# STM32F407ZGT6_1_2.net
KiCad netlist of a schematic drawn in EasyEDA Pro
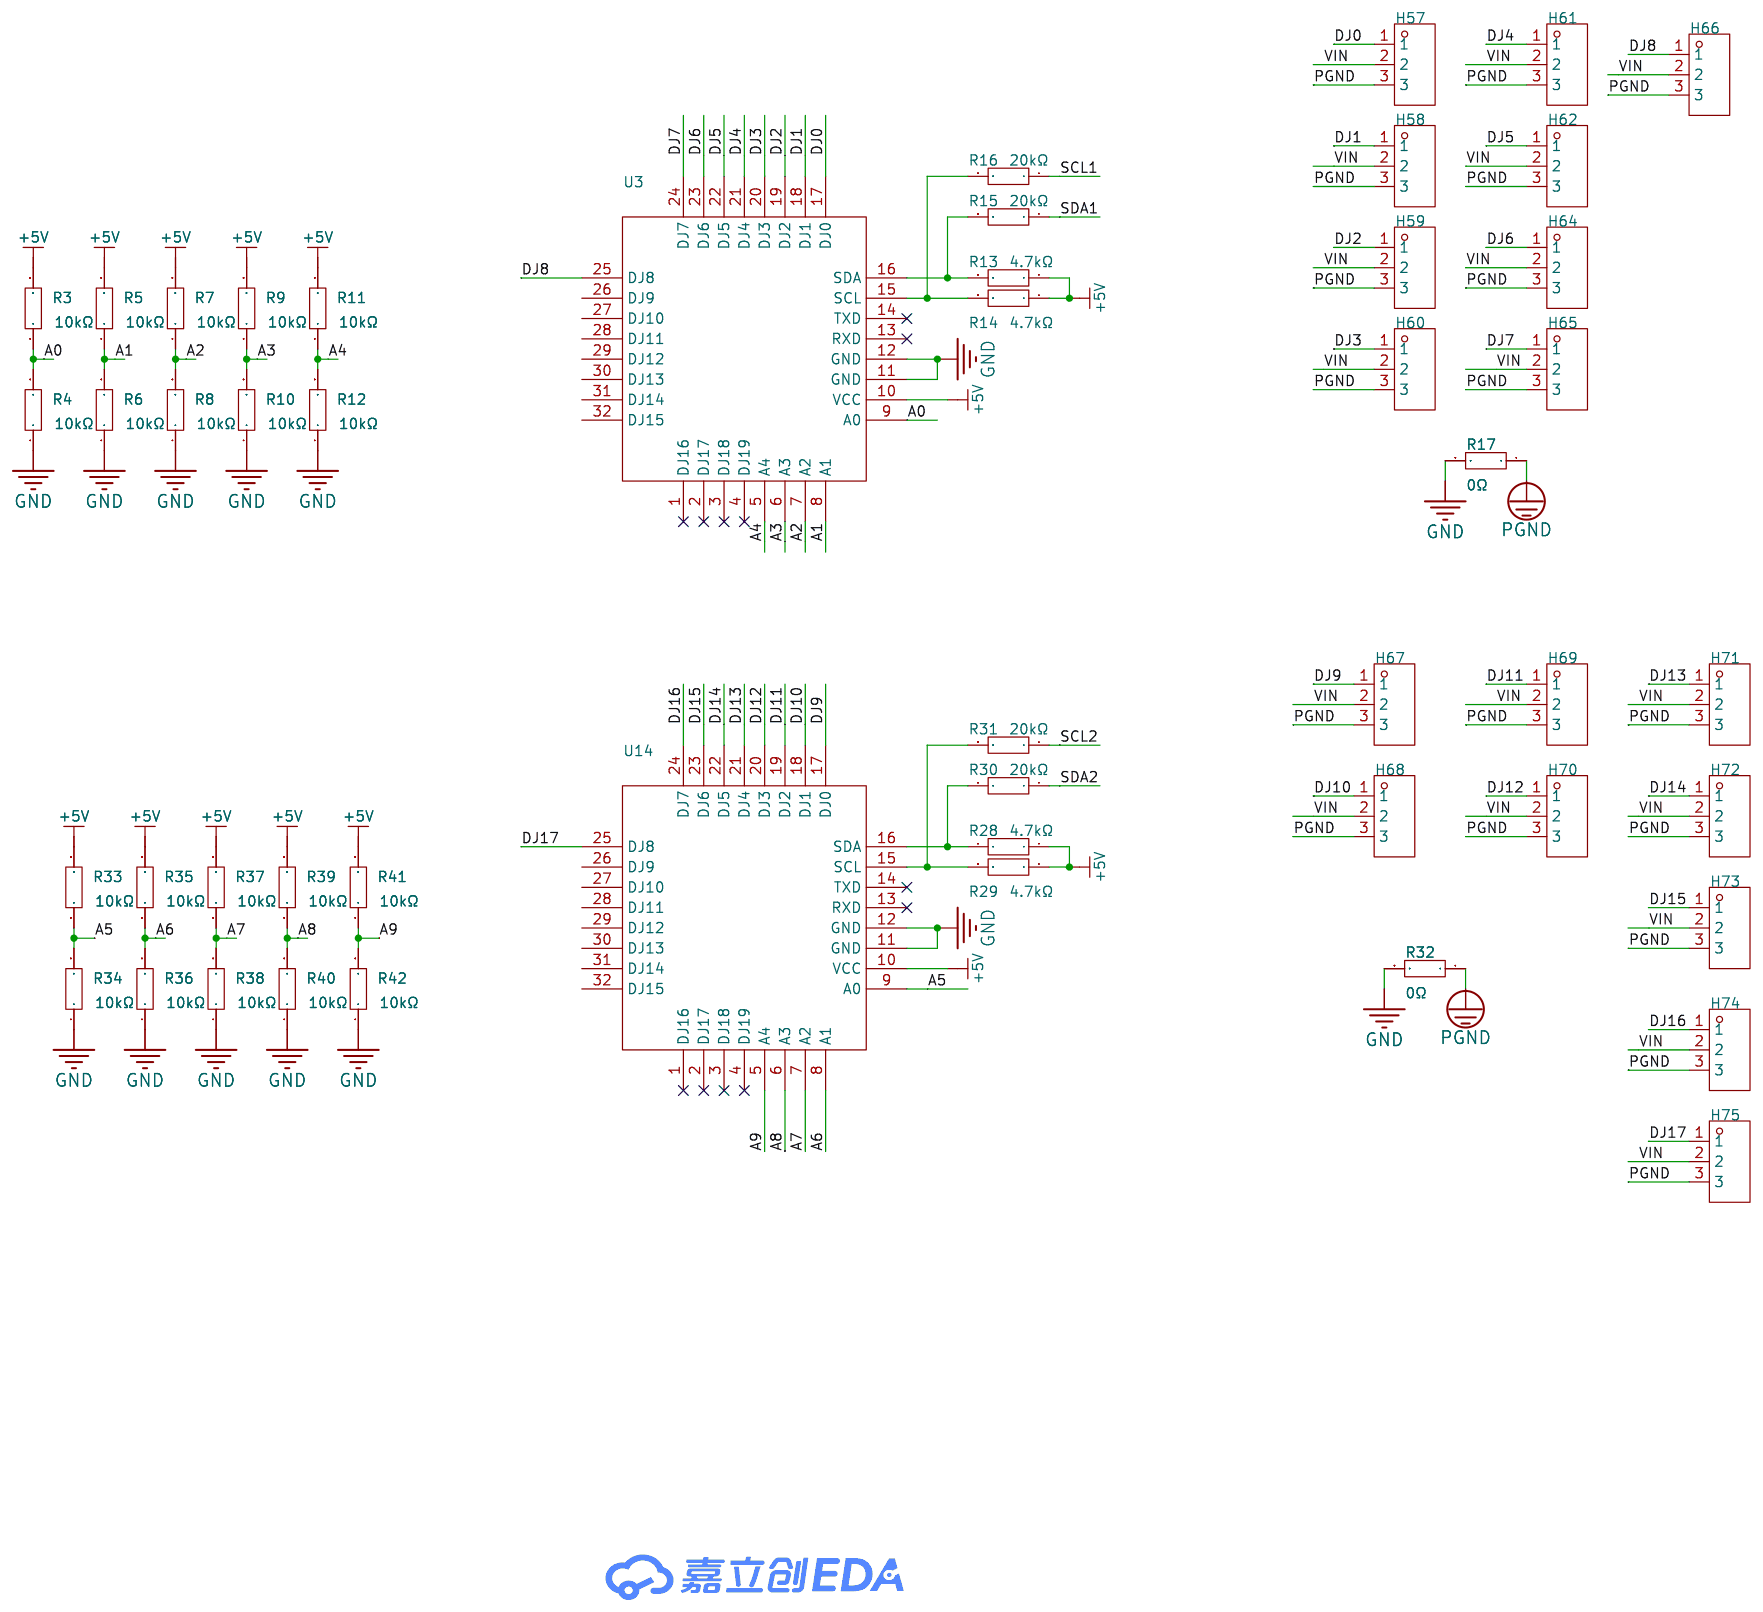
[diagram p0: PWM模块]
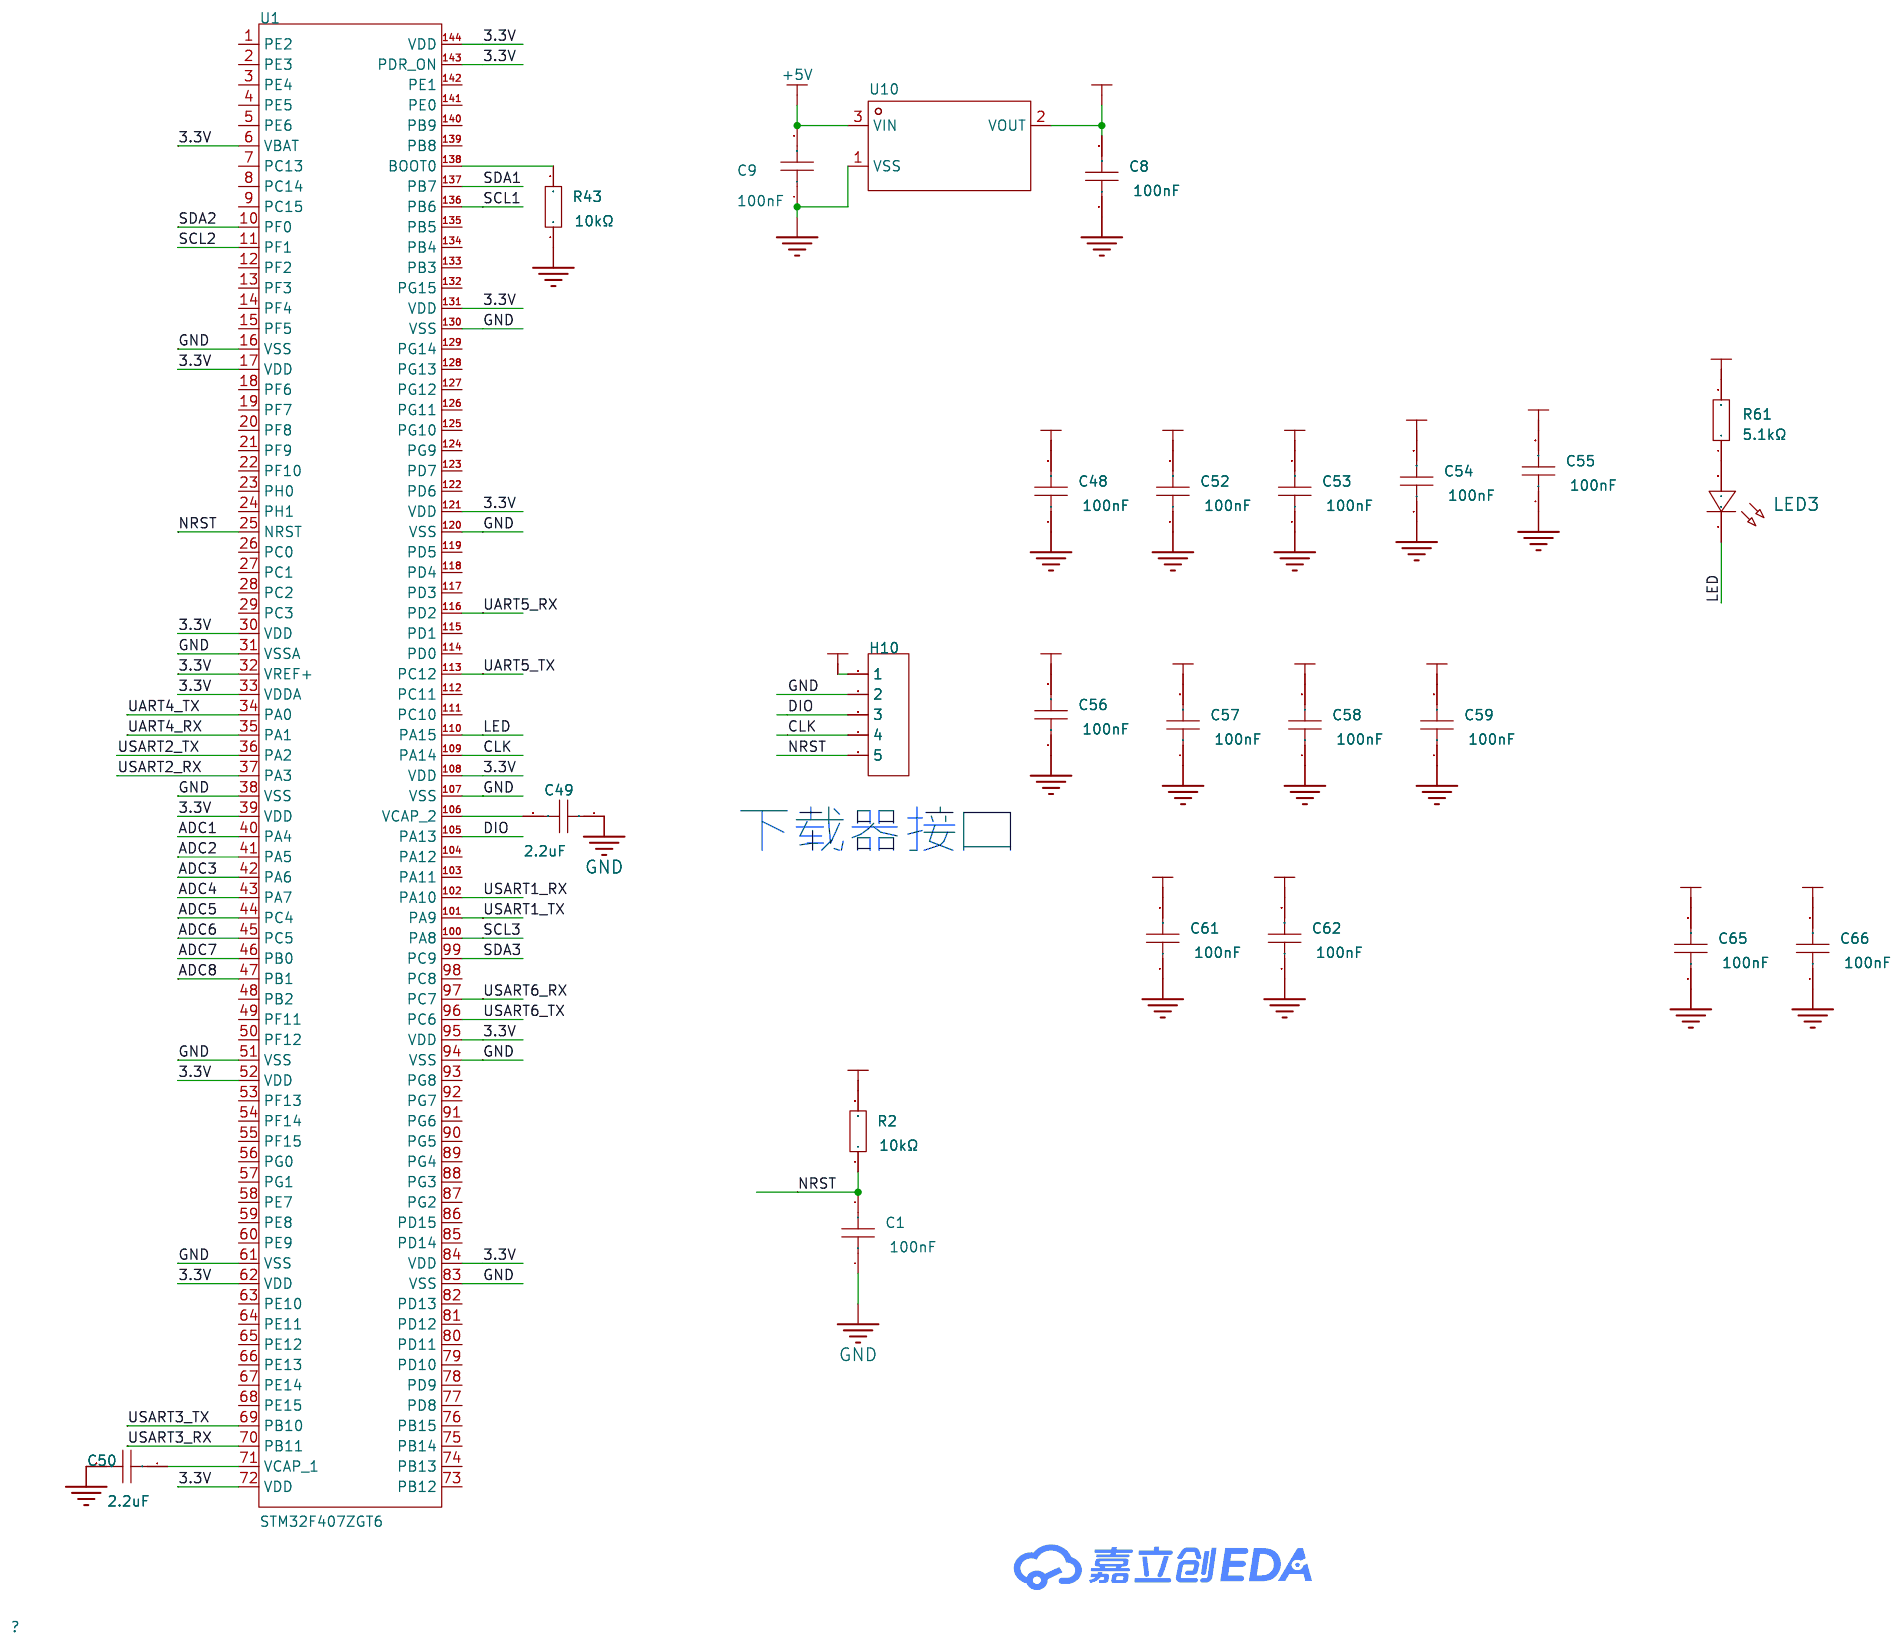
[diagram p1: 单片机模块]
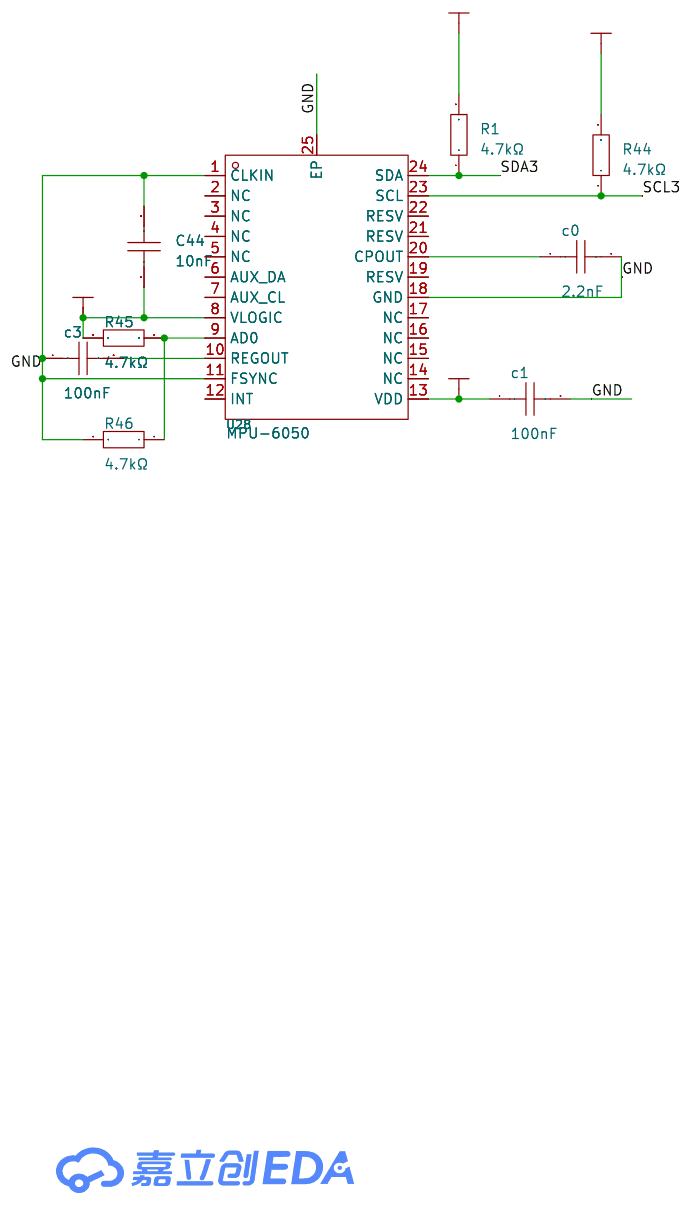
[diagram p2: IMU]
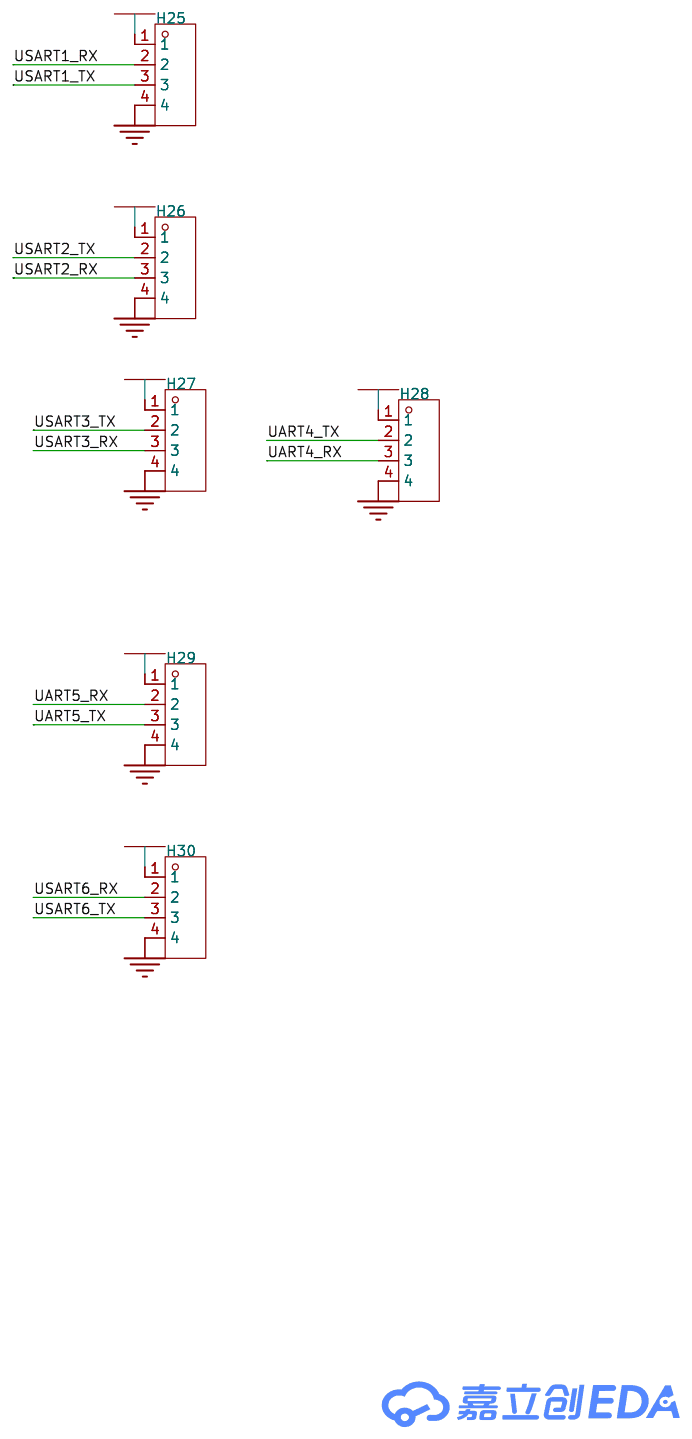
[diagram p3: 串口]
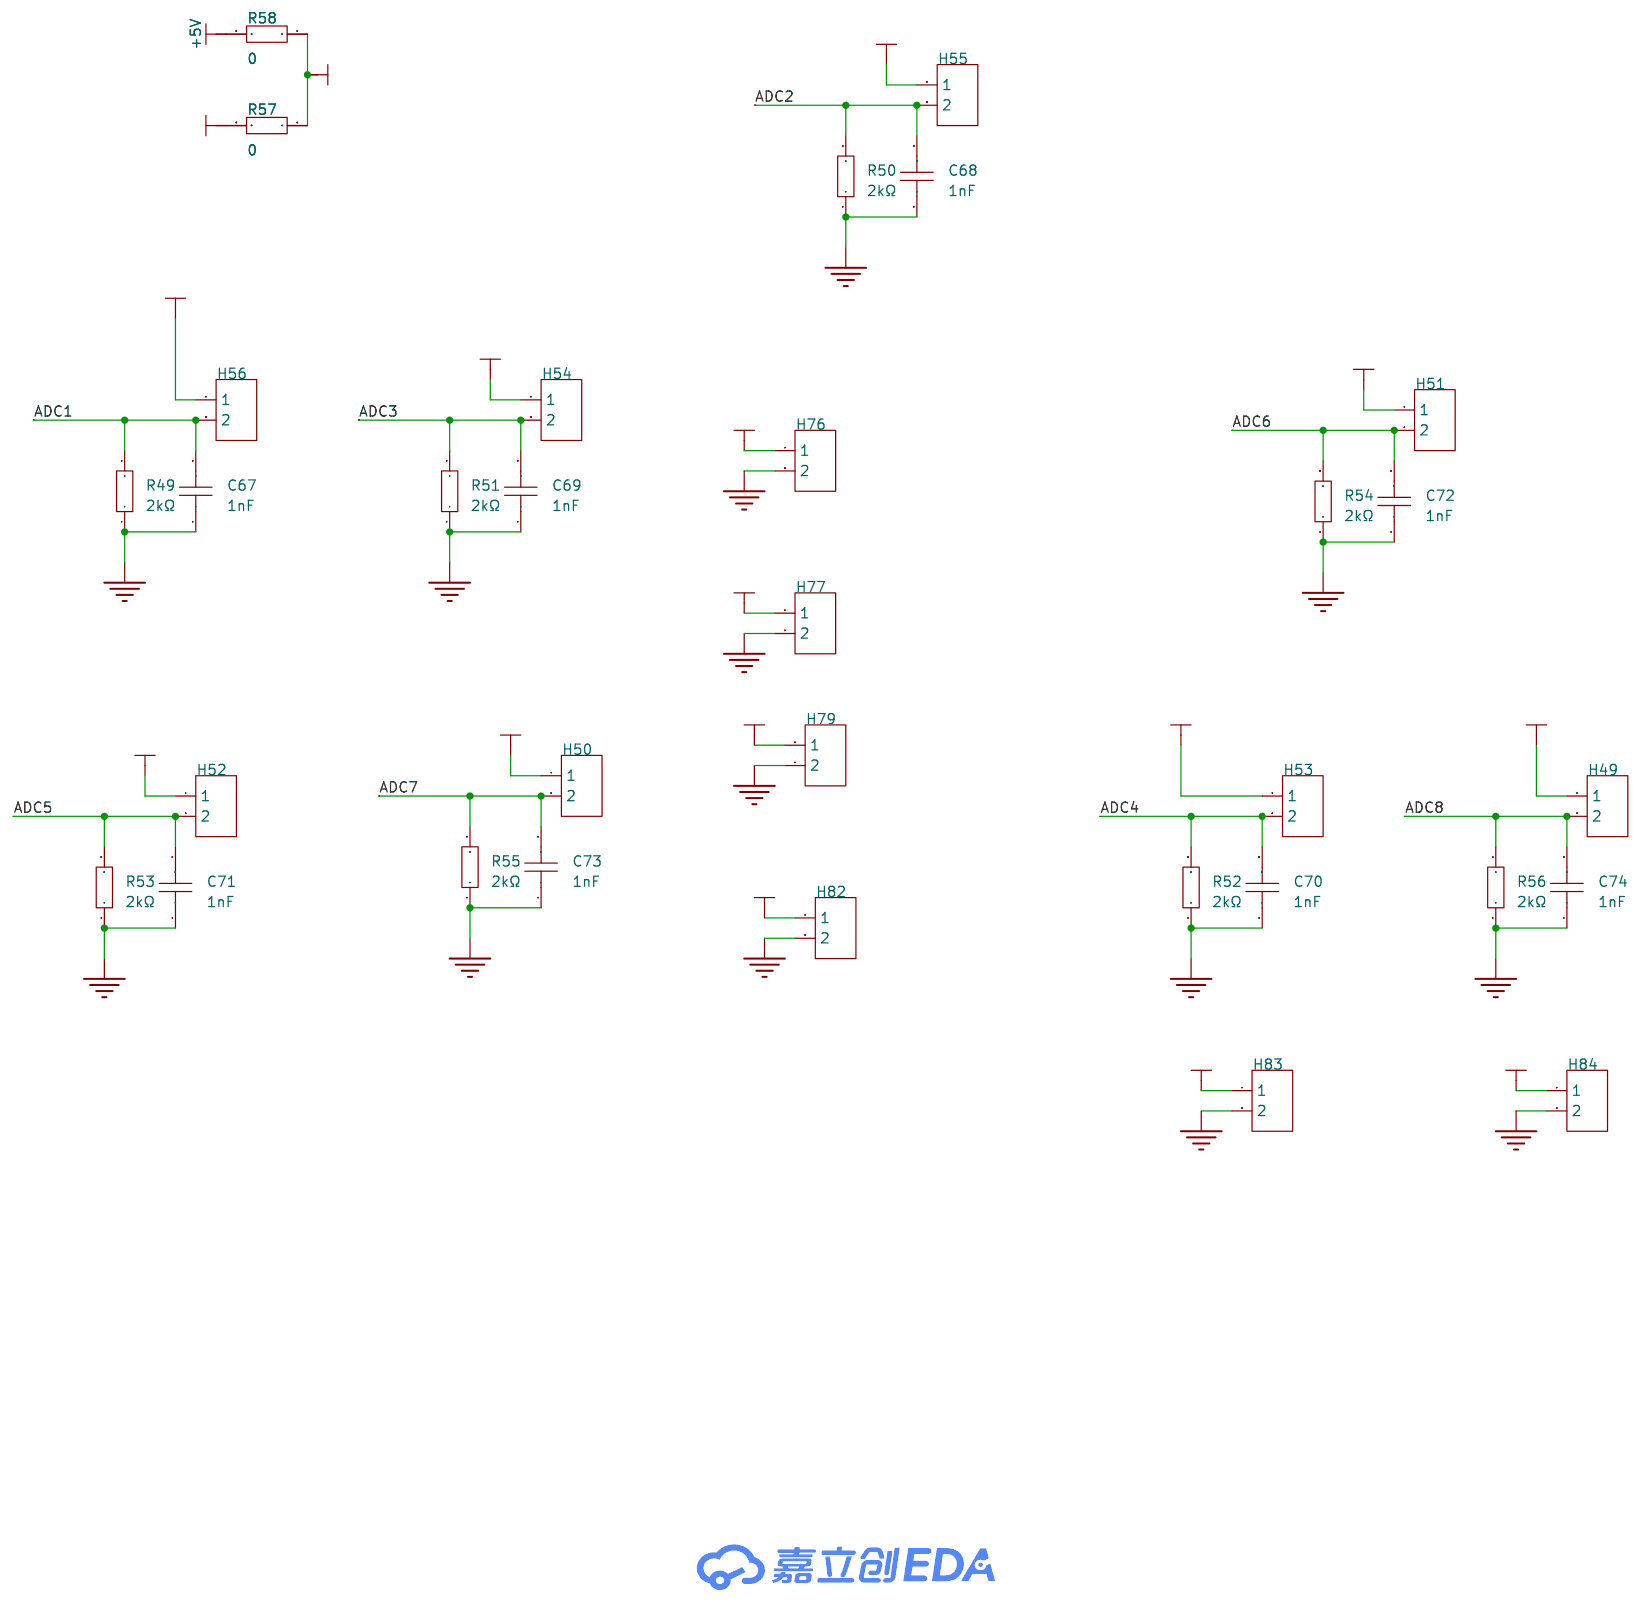
[diagram p4: ADC]
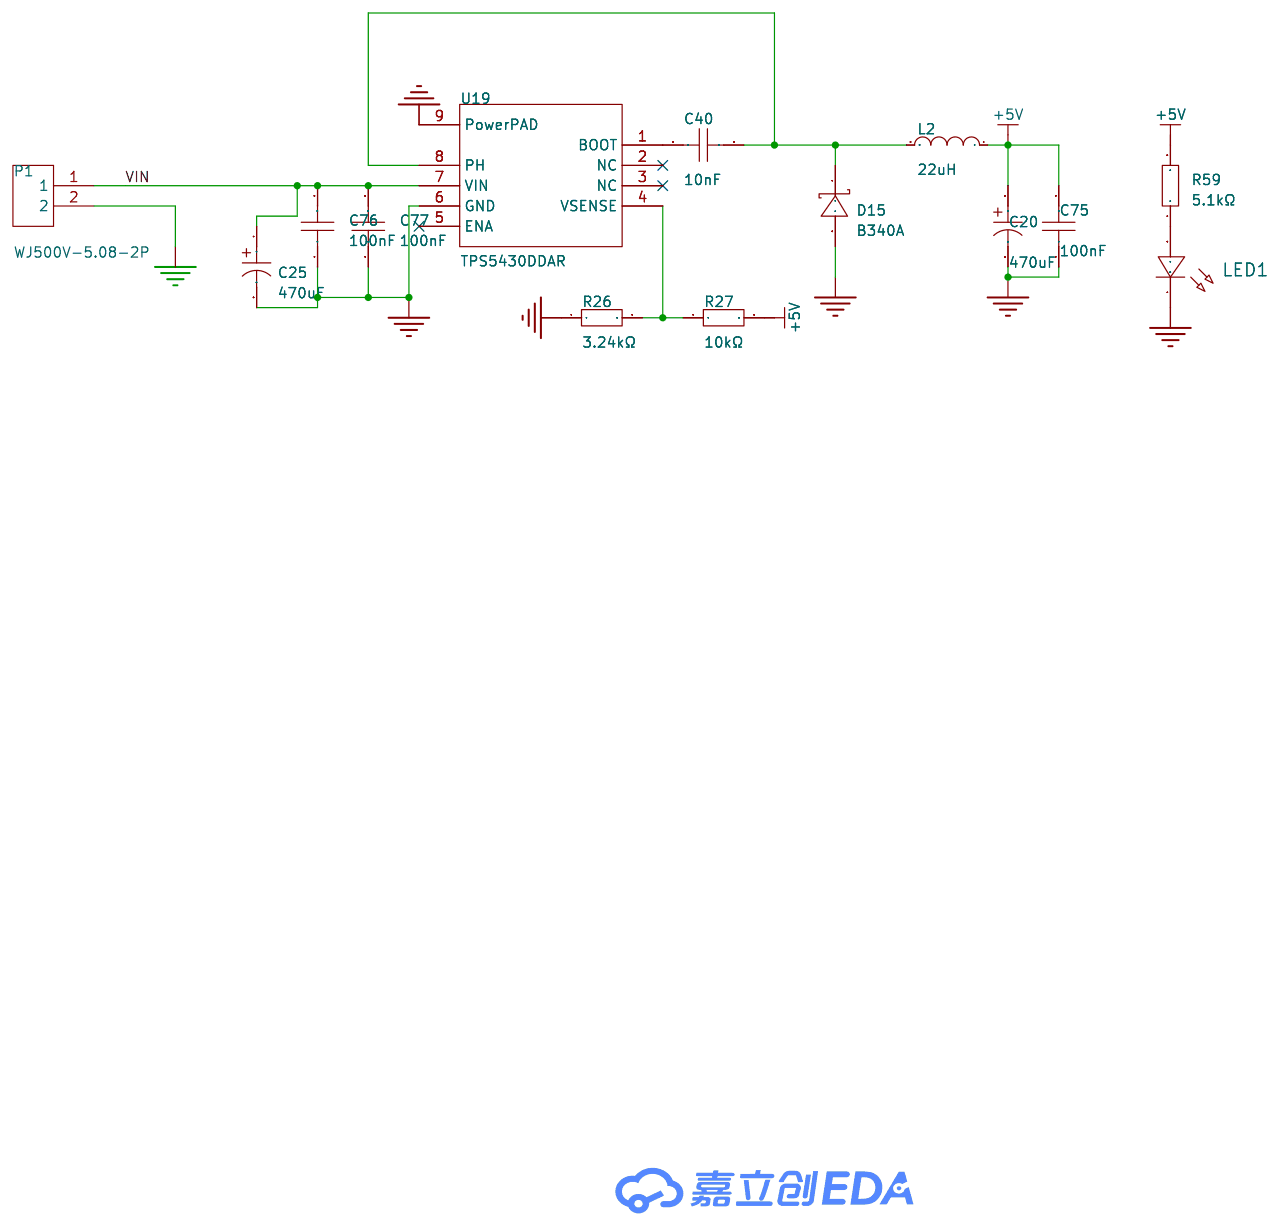
[diagram p5: 电源]

(export (version "E")
  (design (tool "Eeschema 10.0.6"))
  (components
    (comp (ref "H57")
      (value "~")
      (footprint "easyedapro:HDR-TH_3P-P2.54-V-F")
      (libsource (lib "easyedapro") (part "PM254V-11-03-H85"))
    )
    (comp (ref "H58")
      (value "~")
      (footprint "easyedapro:HDR-TH_3P-P2.54-V-F")
      (libsource (lib "easyedapro") (part "PM254V-11-03-H85"))
    )
    (comp (ref "H59")
      (value "~")
      (footprint "easyedapro:HDR-TH_3P-P2.54-V-F")
      (libsource (lib "easyedapro") (part "PM254V-11-03-H85"))
    )
    (comp (ref "H60")
      (value "~")
      (footprint "easyedapro:HDR-TH_3P-P2.54-V-F")
      (libsource (lib "easyedapro") (part "PM254V-11-03-H85"))
    )
    (comp (ref "H61")
      (value "~")
      (footprint "easyedapro:HDR-TH_3P-P2.54-V-F")
      (libsource (lib "easyedapro") (part "PM254V-11-03-H85"))
    )
    (comp (ref "H62")
      (value "~")
      (footprint "easyedapro:HDR-TH_3P-P2.54-V-F")
      (libsource (lib "easyedapro") (part "PM254V-11-03-H85"))
    )
    (comp (ref "H64")
      (value "~")
      (footprint "easyedapro:HDR-TH_3P-P2.54-V-F")
      (libsource (lib "easyedapro") (part "PM254V-11-03-H85"))
    )
    (comp (ref "H65")
      (value "~")
      (footprint "easyedapro:HDR-TH_3P-P2.54-V-F")
      (libsource (lib "easyedapro") (part "PM254V-11-03-H85"))
    )
    (comp (ref "H66")
      (value "~")
      (footprint "easyedapro:HDR-TH_3P-P2.54-V-F")
      (libsource (lib "easyedapro") (part "PM254V-11-03-H85"))
    )
    (comp (ref "H67")
      (value "~")
      (footprint "easyedapro:HDR-TH_3P-P2.54-V-F")
      (libsource (lib "easyedapro") (part "PM254V-11-03-H85"))
    )
    (comp (ref "H68")
      (value "~")
      (footprint "easyedapro:HDR-TH_3P-P2.54-V-F")
      (libsource (lib "easyedapro") (part "PM254V-11-03-H85"))
    )
    (comp (ref "H69")
      (value "~")
      (footprint "easyedapro:HDR-TH_3P-P2.54-V-F")
      (libsource (lib "easyedapro") (part "PM254V-11-03-H85"))
    )
    (comp (ref "H70")
      (value "~")
      (footprint "easyedapro:HDR-TH_3P-P2.54-V-F")
      (libsource (lib "easyedapro") (part "PM254V-11-03-H85"))
    )
    (comp (ref "H71")
      (value "~")
      (footprint "easyedapro:HDR-TH_3P-P2.54-V-F")
      (libsource (lib "easyedapro") (part "PM254V-11-03-H85"))
    )
    (comp (ref "H72")
      (value "~")
      (footprint "easyedapro:HDR-TH_3P-P2.54-V-F")
      (libsource (lib "easyedapro") (part "PM254V-11-03-H85"))
    )
    (comp (ref "H73")
      (value "~")
      (footprint "easyedapro:HDR-TH_3P-P2.54-V-F")
      (libsource (lib "easyedapro") (part "PM254V-11-03-H85"))
    )
    (comp (ref "H74")
      (value "~")
      (footprint "easyedapro:HDR-TH_3P-P2.54-V-F")
      (libsource (lib "easyedapro") (part "PM254V-11-03-H85"))
    )
    (comp (ref "H75")
      (value "~")
      (footprint "easyedapro:HDR-TH_3P-P2.54-V-F")
      (libsource (lib "easyedapro") (part "PM254V-11-03-H85"))
    )
    (comp (ref "R3")
      (value "10kΩ")
      (footprint "easyedapro:R0805")
      (fields
        (field (name "Manufacturer Part") "0402WGF1002TCE")
        (field (name "Manufacturer") "UNI-ROYAL(厚声)")
      )
      (libsource (lib "easyedapro") (part "电阻"))
    )
    (comp (ref "R4")
      (value "10kΩ")
      (footprint "easyedapro:R0805")
      (fields
        (field (name "Manufacturer Part") "0402WGF1002TCE")
        (field (name "Manufacturer") "UNI-ROYAL(厚声)")
      )
      (libsource (lib "easyedapro") (part "电阻"))
    )
    (comp (ref "R5")
      (value "10kΩ")
      (footprint "easyedapro:R0805")
      (fields
        (field (name "Manufacturer Part") "0402WGF1002TCE")
        (field (name "Manufacturer") "UNI-ROYAL(厚声)")
      )
      (libsource (lib "easyedapro") (part "电阻"))
    )
    (comp (ref "R6")
      (value "10kΩ")
      (footprint "easyedapro:R0805")
      (fields
        (field (name "Manufacturer Part") "0402WGF1002TCE")
        (field (name "Manufacturer") "UNI-ROYAL(厚声)")
      )
      (libsource (lib "easyedapro") (part "电阻"))
    )
    (comp (ref "R7")
      (value "10kΩ")
      (footprint "easyedapro:R0805")
      (fields
        (field (name "Manufacturer Part") "0402WGF1002TCE")
        (field (name "Manufacturer") "UNI-ROYAL(厚声)")
      )
      (libsource (lib "easyedapro") (part "电阻"))
    )
    (comp (ref "R8")
      (value "10kΩ")
      (footprint "easyedapro:R0805")
      (fields
        (field (name "Manufacturer Part") "0402WGF1002TCE")
        (field (name "Manufacturer") "UNI-ROYAL(厚声)")
      )
      (libsource (lib "easyedapro") (part "电阻"))
    )
    (comp (ref "R9")
      (value "10kΩ")
      (footprint "easyedapro:R0805")
      (fields
        (field (name "Manufacturer Part") "0402WGF1002TCE")
        (field (name "Manufacturer") "UNI-ROYAL(厚声)")
      )
      (libsource (lib "easyedapro") (part "电阻"))
    )
    (comp (ref "R10")
      (value "10kΩ")
      (footprint "easyedapro:R0805")
      (fields
        (field (name "Manufacturer Part") "0402WGF1002TCE")
        (field (name "Manufacturer") "UNI-ROYAL(厚声)")
      )
      (libsource (lib "easyedapro") (part "电阻"))
    )
    (comp (ref "R11")
      (value "10kΩ")
      (footprint "easyedapro:R0805")
      (fields
        (field (name "Manufacturer Part") "0402WGF1002TCE")
        (field (name "Manufacturer") "UNI-ROYAL(厚声)")
      )
      (libsource (lib "easyedapro") (part "电阻"))
    )
    (comp (ref "R12")
      (value "10kΩ")
      (footprint "easyedapro:R0805")
      (fields
        (field (name "Manufacturer Part") "0402WGF1002TCE")
        (field (name "Manufacturer") "UNI-ROYAL(厚声)")
      )
      (libsource (lib "easyedapro") (part "电阻"))
    )
    (comp (ref "R13")
      (value "4.7kΩ")
      (footprint "easyedapro:R0805")
      (fields
        (field (name "Manufacturer Part") "0402WGF4701TCE")
        (field (name "Manufacturer") "UNI-ROYAL(厚声)")
      )
      (libsource (lib "easyedapro") (part "电阻"))
    )
    (comp (ref "R14")
      (value "4.7kΩ")
      (footprint "easyedapro:R0805")
      (fields
        (field (name "Manufacturer Part") "0402WGF4701TCE")
        (field (name "Manufacturer") "UNI-ROYAL(厚声)")
      )
      (libsource (lib "easyedapro") (part "电阻"))
    )
    (comp (ref "R15")
      (value "20kΩ")
      (footprint "easyedapro:R0805")
      (fields (field (name "Manufacturer Part") "FRC0402F2002TS") (field (name "Manufacturer") "FOJAN(富捷)"))
      (libsource (lib "easyedapro") (part "电阻"))
    )
    (comp (ref "R16")
      (value "20kΩ")
      (footprint "easyedapro:R0805")
      (fields (field (name "Manufacturer Part") "FRC0402F2002TS") (field (name "Manufacturer") "FOJAN(富捷)"))
      (libsource (lib "easyedapro") (part "电阻"))
    )
    (comp (ref "R17")
      (value "0Ω")
      (footprint "easyedapro:R0805")
      (fields
        (field (name "Manufacturer Part") "0402WGF0000TCE")
        (field (name "Manufacturer") "UNI-ROYAL(厚声)")
      )
      (libsource (lib "easyedapro") (part "电阻"))
    )
    (comp (ref "R28")
      (value "4.7kΩ")
      (footprint "easyedapro:R0805")
      (fields
        (field (name "Manufacturer Part") "0402WGF4701TCE")
        (field (name "Manufacturer") "UNI-ROYAL(厚声)")
      )
      (libsource (lib "easyedapro") (part "电阻"))
    )
    (comp (ref "R29")
      (value "4.7kΩ")
      (footprint "easyedapro:R0805")
      (fields
        (field (name "Manufacturer Part") "0402WGF4701TCE")
        (field (name "Manufacturer") "UNI-ROYAL(厚声)")
      )
      (libsource (lib "easyedapro") (part "电阻"))
    )
    (comp (ref "R30")
      (value "20kΩ")
      (footprint "easyedapro:R0805")
      (fields (field (name "Manufacturer Part") "FRC0402F2002TS") (field (name "Manufacturer") "FOJAN(富捷)"))
      (libsource (lib "easyedapro") (part "电阻"))
    )
    (comp (ref "R31")
      (value "20kΩ")
      (footprint "easyedapro:R0805")
      (fields (field (name "Manufacturer Part") "FRC0402F2002TS") (field (name "Manufacturer") "FOJAN(富捷)"))
      (libsource (lib "easyedapro") (part "电阻"))
    )
    (comp (ref "R32")
      (value "0Ω")
      (footprint "easyedapro:R0805")
      (fields
        (field (name "Manufacturer Part") "0402WGF0000TCE")
        (field (name "Manufacturer") "UNI-ROYAL(厚声)")
      )
      (libsource (lib "easyedapro") (part "电阻"))
    )
    (comp (ref "R33")
      (value "10kΩ")
      (footprint "easyedapro:R0805")
      (fields
        (field (name "Manufacturer Part") "0402WGF1002TCE")
        (field (name "Manufacturer") "UNI-ROYAL(厚声)")
      )
      (libsource (lib "easyedapro") (part "电阻"))
    )
    (comp (ref "R34")
      (value "10kΩ")
      (footprint "easyedapro:R0805")
      (fields
        (field (name "Manufacturer Part") "0402WGF1002TCE")
        (field (name "Manufacturer") "UNI-ROYAL(厚声)")
      )
      (libsource (lib "easyedapro") (part "电阻"))
    )
    (comp (ref "R35")
      (value "10kΩ")
      (footprint "easyedapro:R0805")
      (fields
        (field (name "Manufacturer Part") "0402WGF1002TCE")
        (field (name "Manufacturer") "UNI-ROYAL(厚声)")
      )
      (libsource (lib "easyedapro") (part "电阻"))
    )
    (comp (ref "R36")
      (value "10kΩ")
      (footprint "easyedapro:R0805")
      (fields
        (field (name "Manufacturer Part") "0402WGF1002TCE")
        (field (name "Manufacturer") "UNI-ROYAL(厚声)")
      )
      (libsource (lib "easyedapro") (part "电阻"))
    )
    (comp (ref "R37")
      (value "10kΩ")
      (footprint "easyedapro:R0805")
      (fields
        (field (name "Manufacturer Part") "0402WGF1002TCE")
        (field (name "Manufacturer") "UNI-ROYAL(厚声)")
      )
      (libsource (lib "easyedapro") (part "电阻"))
    )
    (comp (ref "R38")
      (value "10kΩ")
      (footprint "easyedapro:R0805")
      (fields
        (field (name "Manufacturer Part") "0402WGF1002TCE")
        (field (name "Manufacturer") "UNI-ROYAL(厚声)")
      )
      (libsource (lib "easyedapro") (part "电阻"))
    )
    (comp (ref "R39")
      (value "10kΩ")
      (footprint "easyedapro:R0805")
      (fields
        (field (name "Manufacturer Part") "0402WGF1002TCE")
        (field (name "Manufacturer") "UNI-ROYAL(厚声)")
      )
      (libsource (lib "easyedapro") (part "电阻"))
    )
    (comp (ref "R40")
      (value "10kΩ")
      (footprint "easyedapro:R0805")
      (fields
        (field (name "Manufacturer Part") "0402WGF1002TCE")
        (field (name "Manufacturer") "UNI-ROYAL(厚声)")
      )
      (libsource (lib "easyedapro") (part "电阻"))
    )
    (comp (ref "R41")
      (value "10kΩ")
      (footprint "easyedapro:R0805")
      (fields
        (field (name "Manufacturer Part") "0402WGF1002TCE")
        (field (name "Manufacturer") "UNI-ROYAL(厚声)")
      )
      (libsource (lib "easyedapro") (part "电阻"))
    )
    (comp (ref "R42")
      (value "10kΩ")
      (footprint "easyedapro:R0805")
      (fields
        (field (name "Manufacturer Part") "0402WGF1002TCE")
        (field (name "Manufacturer") "UNI-ROYAL(厚声)")
      )
      (libsource (lib "easyedapro") (part "电阻"))
    )
    (comp (ref "U3")
      (value "~")
      (description "LU9685 16路舵机驱动芯片代替PCA9685")
      (libsource (lib "easyedapro") (part "LU9685"))
    )
    (comp (ref "U14")
      (value "~")
      (description "LU9685 16路舵机驱动芯片代替PCA9685")
      (libsource (lib "easyedapro") (part "LU9685"))
    )
    (comp (ref "C1")
      (value "100nF")
      (fields
        (field (name "Manufacturer Part") "CL05B104KB54PNC")
        (field (name "Manufacturer") "SAMSUNG(三星)")
      )
      (libsource (lib "easyedapro") (part "CapAcitance"))
    )
    (comp (ref "C8")
      (value "100nF")
      (fields
        (field (name "Manufacturer Part") "CL05B104KB54PNC")
        (field (name "Manufacturer") "SAMSUNG(三星)")
      )
      (libsource (lib "easyedapro") (part "CapAcitance"))
    )
    (comp (ref "C9")
      (value "100nF")
      (fields
        (field (name "Manufacturer Part") "CL05B104KB54PNC")
        (field (name "Manufacturer") "SAMSUNG(三星)")
      )
      (libsource (lib "easyedapro") (part "CapAcitance"))
    )
    (comp (ref "C48")
      (value "100nF")
      (fields
        (field (name "Manufacturer Part") "CL05B104KB54PNC")
        (field (name "Manufacturer") "SAMSUNG(三星)")
      )
      (libsource (lib "easyedapro") (part "CapAcitance"))
    )
    (comp (ref "C49")
      (value "2.2uF")
      (footprint "easyedapro:C0603")
      (fields
        (field (name "Manufacturer Part") "CL05A225KO5NQNC")
        (field (name "Manufacturer") "SAMSUNG(三星)")
      )
      (libsource (lib "easyedapro") (part "CapAcitance"))
    )
    (comp (ref "C50")
      (value "2.2uF")
      (footprint "easyedapro:C0603")
      (fields
        (field (name "Manufacturer Part") "CL05A225KO5NQNC")
        (field (name "Manufacturer") "SAMSUNG(三星)")
      )
      (libsource (lib "easyedapro") (part "CapAcitance"))
    )
    (comp (ref "C52")
      (value "100nF")
      (fields
        (field (name "Manufacturer Part") "CL05B104KB54PNC")
        (field (name "Manufacturer") "SAMSUNG(三星)")
      )
      (libsource (lib "easyedapro") (part "CapAcitance"))
    )
    (comp (ref "C53")
      (value "100nF")
      (fields
        (field (name "Manufacturer Part") "CL05B104KB54PNC")
        (field (name "Manufacturer") "SAMSUNG(三星)")
      )
      (libsource (lib "easyedapro") (part "CapAcitance"))
    )
    (comp (ref "C54")
      (value "100nF")
      (fields
        (field (name "Manufacturer Part") "CL05B104KB54PNC")
        (field (name "Manufacturer") "SAMSUNG(三星)")
      )
      (libsource (lib "easyedapro") (part "CapAcitance"))
    )
    (comp (ref "C55")
      (value "100nF")
      (fields
        (field (name "Manufacturer Part") "CL05B104KB54PNC")
        (field (name "Manufacturer") "SAMSUNG(三星)")
      )
      (libsource (lib "easyedapro") (part "CapAcitance"))
    )
    (comp (ref "C56")
      (value "100nF")
      (fields
        (field (name "Manufacturer Part") "CL05B104KB54PNC")
        (field (name "Manufacturer") "SAMSUNG(三星)")
      )
      (libsource (lib "easyedapro") (part "CapAcitance"))
    )
    (comp (ref "C57")
      (value "100nF")
      (fields
        (field (name "Manufacturer Part") "CL05B104KB54PNC")
        (field (name "Manufacturer") "SAMSUNG(三星)")
      )
      (libsource (lib "easyedapro") (part "CapAcitance"))
    )
    (comp (ref "C58")
      (value "100nF")
      (fields
        (field (name "Manufacturer Part") "CL05B104KB54PNC")
        (field (name "Manufacturer") "SAMSUNG(三星)")
      )
      (libsource (lib "easyedapro") (part "CapAcitance"))
    )
    (comp (ref "C59")
      (value "100nF")
      (fields
        (field (name "Manufacturer Part") "CL05B104KB54PNC")
        (field (name "Manufacturer") "SAMSUNG(三星)")
      )
      (libsource (lib "easyedapro") (part "CapAcitance"))
    )
    (comp (ref "C61")
      (value "100nF")
      (fields
        (field (name "Manufacturer Part") "CL05B104KB54PNC")
        (field (name "Manufacturer") "SAMSUNG(三星)")
      )
      (libsource (lib "easyedapro") (part "CapAcitance"))
    )
    (comp (ref "C62")
      (value "100nF")
      (fields
        (field (name "Manufacturer Part") "CL05B104KB54PNC")
        (field (name "Manufacturer") "SAMSUNG(三星)")
      )
      (libsource (lib "easyedapro") (part "CapAcitance"))
    )
    (comp (ref "C65")
      (value "100nF")
      (fields
        (field (name "Manufacturer Part") "CL05B104KB54PNC")
        (field (name "Manufacturer") "SAMSUNG(三星)")
      )
      (libsource (lib "easyedapro") (part "CapAcitance"))
    )
    (comp (ref "C66")
      (value "100nF")
      (fields
        (field (name "Manufacturer Part") "CL05B104KB54PNC")
        (field (name "Manufacturer") "SAMSUNG(三星)")
      )
      (libsource (lib "easyedapro") (part "CapAcitance"))
    )
    (comp (ref "H10")
      (value "~")
      (footprint "easyedapro:HDR-TH_5P-P2.54-V-F")
      (libsource (lib "easyedapro") (part "Header-Female-2.54_1x5"))
    )
    (comp (ref "LED3")
      (value "~")
      (footprint "easyedapro:LED_0402")
      (libsource (lib "easyedapro") (part "LED_R"))
    )
    (comp (ref "R2")
      (value "10kΩ")
      (fields
        (field (name "Manufacturer Part") "0402WGF1002TCE")
        (field (name "Manufacturer") "UNI-ROYAL(厚声)")
      )
      (libsource (lib "easyedapro") (part "电阻"))
    )
    (comp (ref "R43")
      (value "10kΩ")
      (fields
        (field (name "Manufacturer Part") "0402WGF1002TCE")
        (field (name "Manufacturer") "UNI-ROYAL(厚声)")
      )
      (libsource (lib "easyedapro") (part "电阻"))
    )
    (comp (ref "R61")
      (value "5.1kΩ")
      (footprint "easyedapro:R0603")
      (fields
        (field (name "Manufacturer Part") "0402WGF1002TCE")
        (field (name "Manufacturer") "UNI-ROYAL(厚声)")
      )
      (libsource (lib "easyedapro") (part "电阻"))
    )
    (comp (ref "U1")
      (value "STM32F407ZGT6")
      (footprint "easyedapro:LQFP-144_L20.0-W20.0-P0.50-LS22.0-BL")
      (description "CPU内核:ARM-M4;CPU最大主频:168MHz;应用领域:-;")
      (fields (field (name "Manufacturer") "ST(意法半导体)"))
      (libsource (lib "easyedapro") (part "STM32F407ZGT6"))
    )
    (comp (ref "U10")
      (value "ME6211A33M3G-N")
      (footprint "easyedapro:SOT-23-3_L2.9-W1.6-P1.90-LS2.8-BR")
      (description "输出类型:固定;输出极性:正;最大输入电压:6V;输出电压:3.3V;输出电流:500mA;电源纹波抑制比(PSRR):70dB;")
      (fields (field (name "Manufacturer") "MICRONE(南京微盟)"))
      (libsource (lib "easyedapro") (part "ME6211A33M3G-N"))
    )
    (comp (ref "c0")
      (value "2.2nF")
      (footprint "easyedapro:C0603")
      (fields
        (field (name "Manufacturer Part") "GRM1555C1H222GA01D")
        (field (name "Manufacturer") "muRata(村田)")
      )
      (libsource (lib "easyedapro") (part "CapAcitance"))
    )
    (comp (ref "c1")
      (value "100nF")
      (footprint "easyedapro:C0603")
      (fields
        (field (name "Manufacturer Part") "CL05B104KB54PNC")
        (field (name "Manufacturer") "SAMSUNG(三星)")
      )
      (libsource (lib "easyedapro") (part "CapAcitance"))
    )
    (comp (ref "c3")
      (value "100nF")
      (footprint "easyedapro:C0603")
      (fields
        (field (name "Manufacturer Part") "CL05B104KB54PNC")
        (field (name "Manufacturer") "SAMSUNG(三星)")
      )
      (libsource (lib "easyedapro") (part "CapAcitance"))
    )
    (comp (ref "C44")
      (value "10nF")
      (footprint "easyedapro:C0603")
      (fields
        (field (name "Manufacturer Part") "CL05B103KB5NNNC")
        (field (name "Manufacturer") "SAMSUNG(三星)")
      )
      (libsource (lib "easyedapro") (part "CapAcitance"))
    )
    (comp (ref "R1")
      (value "4.7kΩ")
      (footprint "easyedapro:R0603")
      (fields
        (field (name "Manufacturer Part") "0402WGF4701TCE")
        (field (name "Manufacturer") "UNI-ROYAL(厚声)")
      )
      (libsource (lib "easyedapro") (part "电阻"))
    )
    (comp (ref "R44")
      (value "4.7kΩ")
      (footprint "easyedapro:R0603")
      (fields
        (field (name "Manufacturer Part") "0402WGF4701TCE")
        (field (name "Manufacturer") "UNI-ROYAL(厚声)")
      )
      (libsource (lib "easyedapro") (part "电阻"))
    )
    (comp (ref "R45")
      (value "4.7kΩ")
      (footprint "easyedapro:R0603")
      (fields
        (field (name "Manufacturer Part") "0402WGF4701TCE")
        (field (name "Manufacturer") "UNI-ROYAL(厚声)")
      )
      (libsource (lib "easyedapro") (part "电阻"))
    )
    (comp (ref "R46")
      (value "4.7kΩ")
      (footprint "easyedapro:R0603")
      (fields
        (field (name "Manufacturer Part") "0402WGF4701TCE")
        (field (name "Manufacturer") "UNI-ROYAL(厚声)")
      )
      (libsource (lib "easyedapro") (part "电阻"))
    )
    (comp (ref "U28")
      (value "MPU-6050")
      (footprint "easyedapro:QFN-24_L4.0-W4.0-P0.50-BL-EP2.7")
      (description "三轴加速度计和三轴陀螺仪，工作电压：2.375V~3.46V")
      (fields (field (name "Manufacturer") "TDK InvenSense(应美盛)"))
      (libsource (lib "easyedapro") (part "MPU-6050_C24112"))
    )
    (comp (ref "H25")
      (value "~")
      (footprint "easyedapro:HDR-TH_4P-P2.54-V-F")
      (libsource (lib "easyedapro") (part "2.54-1*4P母"))
    )
    (comp (ref "H26")
      (value "~")
      (footprint "easyedapro:HDR-TH_4P-P2.54-V-F")
      (libsource (lib "easyedapro") (part "2.54-1*4P母"))
    )
    (comp (ref "H27")
      (value "~")
      (footprint "easyedapro:HDR-TH_4P-P2.54-V-F")
      (libsource (lib "easyedapro") (part "2.54-1*4P母"))
    )
    (comp (ref "H28")
      (value "~")
      (footprint "easyedapro:HDR-TH_4P-P2.54-V-F")
      (libsource (lib "easyedapro") (part "2.54-1*4P母"))
    )
    (comp (ref "H29")
      (value "~")
      (footprint "easyedapro:HDR-TH_4P-P2.54-V-F")
      (libsource (lib "easyedapro") (part "2.54-1*4P母"))
    )
    (comp (ref "H30")
      (value "~")
      (footprint "easyedapro:HDR-TH_4P-P2.54-V-F")
      (libsource (lib "easyedapro") (part "2.54-1*4P母"))
    )
    (comp (ref "C67")
      (value "1nF")
      (footprint "easyedapro:C0603")
      (fields
        (field (name "Manufacturer Part") "FCC0402B102K500AT")
        (field (name "Manufacturer") "FOJAN(富捷)")
      )
      (libsource (lib "easyedapro") (part "CapAcitance"))
    )
    (comp (ref "C68")
      (value "1nF")
      (footprint "easyedapro:C0603")
      (fields
        (field (name "Manufacturer Part") "FCC0402B102K500AT")
        (field (name "Manufacturer") "FOJAN(富捷)")
      )
      (libsource (lib "easyedapro") (part "CapAcitance"))
    )
    (comp (ref "C69")
      (value "1nF")
      (footprint "easyedapro:C0603")
      (fields
        (field (name "Manufacturer Part") "FCC0402B102K500AT")
        (field (name "Manufacturer") "FOJAN(富捷)")
      )
      (libsource (lib "easyedapro") (part "CapAcitance"))
    )
    (comp (ref "C70")
      (value "1nF")
      (footprint "easyedapro:C0603")
      (fields
        (field (name "Manufacturer Part") "FCC0402B102K500AT")
        (field (name "Manufacturer") "FOJAN(富捷)")
      )
      (libsource (lib "easyedapro") (part "CapAcitance"))
    )
    (comp (ref "C71")
      (value "1nF")
      (footprint "easyedapro:C0603")
      (fields
        (field (name "Manufacturer Part") "FCC0402B102K500AT")
        (field (name "Manufacturer") "FOJAN(富捷)")
      )
      (libsource (lib "easyedapro") (part "CapAcitance"))
    )
    (comp (ref "C72")
      (value "1nF")
      (footprint "easyedapro:C0603")
      (fields
        (field (name "Manufacturer Part") "FCC0402B102K500AT")
        (field (name "Manufacturer") "FOJAN(富捷)")
      )
      (libsource (lib "easyedapro") (part "CapAcitance"))
    )
    (comp (ref "C73")
      (value "1nF")
      (footprint "easyedapro:C0603")
      (fields
        (field (name "Manufacturer Part") "FCC0402B102K500AT")
        (field (name "Manufacturer") "FOJAN(富捷)")
      )
      (libsource (lib "easyedapro") (part "CapAcitance"))
    )
    (comp (ref "C74")
      (value "1nF")
      (footprint "easyedapro:C0603")
      (fields
        (field (name "Manufacturer Part") "FCC0402B102K500AT")
        (field (name "Manufacturer") "FOJAN(富捷)")
      )
      (libsource (lib "easyedapro") (part "CapAcitance"))
    )
    (comp (ref "H49")
      (value "~")
      (footprint "easyedapro:HDR-TH_2P-P2.54-V-F")
      (libsource (lib "easyedapro") (part "Header-Female-2.54_1x2"))
    )
    (comp (ref "H50")
      (value "~")
      (footprint "easyedapro:HDR-TH_2P-P2.54-V-F")
      (libsource (lib "easyedapro") (part "Header-Female-2.54_1x2"))
    )
    (comp (ref "H51")
      (value "~")
      (footprint "easyedapro:HDR-TH_2P-P2.54-V-F")
      (libsource (lib "easyedapro") (part "Header-Female-2.54_1x2"))
    )
    (comp (ref "H52")
      (value "~")
      (footprint "easyedapro:HDR-TH_2P-P2.54-V-F")
      (libsource (lib "easyedapro") (part "Header-Female-2.54_1x2"))
    )
    (comp (ref "H53")
      (value "~")
      (footprint "easyedapro:HDR-TH_2P-P2.54-V-F")
      (libsource (lib "easyedapro") (part "Header-Female-2.54_1x2"))
    )
    (comp (ref "H54")
      (value "~")
      (footprint "easyedapro:HDR-TH_2P-P2.54-V-F")
      (libsource (lib "easyedapro") (part "Header-Female-2.54_1x2"))
    )
    (comp (ref "H55")
      (value "~")
      (footprint "easyedapro:HDR-TH_2P-P2.54-V-F")
      (libsource (lib "easyedapro") (part "Header-Female-2.54_1x2"))
    )
    (comp (ref "H56")
      (value "~")
      (footprint "easyedapro:HDR-TH_2P-P2.54-V-F")
      (libsource (lib "easyedapro") (part "Header-Female-2.54_1x2"))
    )
    (comp (ref "H76")
      (value "~")
      (footprint "easyedapro:HDR-TH_2P-P2.54-V-F")
      (libsource (lib "easyedapro") (part "Header-Female-2.54_1x2"))
    )
    (comp (ref "H77")
      (value "~")
      (footprint "easyedapro:HDR-TH_2P-P2.54-V-F")
      (libsource (lib "easyedapro") (part "Header-Female-2.54_1x2"))
    )
    (comp (ref "H79")
      (value "~")
      (footprint "easyedapro:HDR-TH_2P-P2.54-V-F")
      (libsource (lib "easyedapro") (part "Header-Female-2.54_1x2"))
    )
    (comp (ref "H82")
      (value "~")
      (footprint "easyedapro:HDR-TH_2P-P2.54-V-F")
      (libsource (lib "easyedapro") (part "Header-Female-2.54_1x2"))
    )
    (comp (ref "H83")
      (value "~")
      (footprint "easyedapro:HDR-TH_2P-P2.54-V-F")
      (libsource (lib "easyedapro") (part "Header-Female-2.54_1x2"))
    )
    (comp (ref "H84")
      (value "~")
      (footprint "easyedapro:HDR-TH_2P-P2.54-V-F")
      (libsource (lib "easyedapro") (part "Header-Female-2.54_1x2"))
    )
    (comp (ref "R49")
      (value "2kΩ")
      (footprint "easyedapro:R0603")
      (fields
        (field (name "Manufacturer Part") "0402WGF2001TCE")
        (field (name "Manufacturer") "UNI-ROYAL(厚声)")
      )
      (libsource (lib "easyedapro") (part "电阻"))
    )
    (comp (ref "R50")
      (value "2kΩ")
      (footprint "easyedapro:R0603")
      (fields
        (field (name "Manufacturer Part") "0402WGF2001TCE")
        (field (name "Manufacturer") "UNI-ROYAL(厚声)")
      )
      (libsource (lib "easyedapro") (part "电阻"))
    )
    (comp (ref "R51")
      (value "2kΩ")
      (footprint "easyedapro:R0603")
      (fields
        (field (name "Manufacturer Part") "0402WGF2001TCE")
        (field (name "Manufacturer") "UNI-ROYAL(厚声)")
      )
      (libsource (lib "easyedapro") (part "电阻"))
    )
    (comp (ref "R52")
      (value "2kΩ")
      (footprint "easyedapro:R0603")
      (fields
        (field (name "Manufacturer Part") "0402WGF2001TCE")
        (field (name "Manufacturer") "UNI-ROYAL(厚声)")
      )
      (libsource (lib "easyedapro") (part "电阻"))
    )
    (comp (ref "R53")
      (value "2kΩ")
      (footprint "easyedapro:R0603")
      (fields
        (field (name "Manufacturer Part") "0402WGF2001TCE")
        (field (name "Manufacturer") "UNI-ROYAL(厚声)")
      )
      (libsource (lib "easyedapro") (part "电阻"))
    )
    (comp (ref "R54")
      (value "2kΩ")
      (footprint "easyedapro:R0603")
      (fields
        (field (name "Manufacturer Part") "0402WGF2001TCE")
        (field (name "Manufacturer") "UNI-ROYAL(厚声)")
      )
      (libsource (lib "easyedapro") (part "电阻"))
    )
    (comp (ref "R55")
      (value "2kΩ")
      (footprint "easyedapro:R0603")
      (fields
        (field (name "Manufacturer Part") "0402WGF2001TCE")
        (field (name "Manufacturer") "UNI-ROYAL(厚声)")
      )
      (libsource (lib "easyedapro") (part "电阻"))
    )
    (comp (ref "R56")
      (value "2kΩ")
      (footprint "easyedapro:R0603")
      (fields
        (field (name "Manufacturer Part") "0402WGF2001TCE")
        (field (name "Manufacturer") "UNI-ROYAL(厚声)")
      )
      (libsource (lib "easyedapro") (part "电阻"))
    )
    (comp (ref "R57")
      (value "0")
      (footprint "easyedapro:R0603")
      (fields
        (field (name "Manufacturer Part") "0402WGF2001TCE")
        (field (name "Manufacturer") "UNI-ROYAL(厚声)")
      )
      (libsource (lib "easyedapro") (part "电阻"))
    )
    (comp (ref "R58")
      (value "0")
      (footprint "easyedapro:R0603")
      (fields
        (field (name "Manufacturer Part") "0402WGF2001TCE")
        (field (name "Manufacturer") "UNI-ROYAL(厚声)")
      )
      (libsource (lib "easyedapro") (part "电阻"))
    )
    (comp (ref "C20")
      (value "470uF")
      (fields
        (field (name "Manufacturer Part") "EGT477M1HG16RRS0P")
        (field (name "Manufacturer") "MAN YUE(万裕科技)")
      )
      (libsource (lib "easyedapro") (part "RST470UF10V029"))
    )
    (comp (ref "C25")
      (value "470uF")
      (fields
        (field (name "Manufacturer Part") "EGT477M1HG16RRS0P")
        (field (name "Manufacturer") "MAN YUE(万裕科技)")
      )
      (libsource (lib "easyedapro") (part "RST470UF10V029"))
    )
    (comp (ref "C40")
      (value "10nF")
      (footprint "easyedapro:C0603")
      (fields
        (field (name "Manufacturer Part") "CL05B103KB5NNNC")
        (field (name "Manufacturer") "SAMSUNG(三星)")
      )
      (libsource (lib "easyedapro") (part "CapAcitance"))
    )
    (comp (ref "C75")
      (value "100nF")
      (footprint "easyedapro:C0603")
      (fields
        (field (name "Manufacturer Part") "CL05B104KB54PNC")
        (field (name "Manufacturer") "SAMSUNG(三星)")
      )
      (libsource (lib "easyedapro") (part "CapAcitance"))
    )
    (comp (ref "C76")
      (value "100nF")
      (footprint "easyedapro:C0603")
      (fields
        (field (name "Manufacturer Part") "CL05B104KB54PNC")
        (field (name "Manufacturer") "SAMSUNG(三星)")
      )
      (libsource (lib "easyedapro") (part "CapAcitance"))
    )
    (comp (ref "C77")
      (value "100nF")
      (footprint "easyedapro:C0603")
      (fields
        (field (name "Manufacturer Part") "CL05B104KB54PNC")
        (field (name "Manufacturer") "SAMSUNG(三星)")
      )
      (libsource (lib "easyedapro") (part "CapAcitance"))
    )
    (comp (ref "D15")
      (value "B340A")
      (footprint "easyedapro:SMA_L4.3-W2.6-LS5.1-RD")
      (description "二极管配置:独立式;正向压降(Vf):550mV@3A;直流反向耐压(Vr):40V;整流电流:3A;")
      (fields (field (name "Manufacturer") "MDD(辰达半导体)"))
      (libsource (lib "easyedapro") (part "B340A"))
    )
    (comp (ref "L2")
      (value "22uH")
      (fields
        (field (name "Manufacturer Part") "CXP0630-220M-AG(22uh)")
        (field (name "Manufacturer") "DMBJ(振宝佳)")
      )
      (libsource (lib "easyedapro") (part "YPRH0704-100M"))
    )
    (comp (ref "LED1")
      (value "~")
      (footprint "easyedapro:LED_0402")
      (libsource (lib "easyedapro") (part "LED_R"))
    )
    (comp (ref "P1")
      (value "WJ500V-5.08-2P")
      (footprint "easyedapro:CONN-TH_2P-P5.00_WJ500V-5.08-2P")
      (fields (field (name "Manufacturer") "KANGNEX(康奈克斯电气)"))
      (libsource (lib "easyedapro") (part "WJ500V-5.08-2P-14-00A"))
    )
    (comp (ref "R26")
      (value "3.24kΩ")
      (footprint "easyedapro:R0603")
      (fields
        (field (name "Manufacturer Part") "0402WGF3241TCE")
        (field (name "Manufacturer") "UNI-ROYAL(厚声)")
      )
      (libsource (lib "easyedapro") (part "电阻"))
    )
    (comp (ref "R27")
      (value "10kΩ")
      (footprint "easyedapro:R0603")
      (fields
        (field (name "Manufacturer Part") "0402WGF1002TCE")
        (field (name "Manufacturer") "UNI-ROYAL(厚声)")
      )
      (libsource (lib "easyedapro") (part "电阻"))
    )
    (comp (ref "R59")
      (value "5.1kΩ")
      (footprint "easyedapro:R0603")
      (fields
        (field (name "Manufacturer Part") "0402WGF1002TCE")
        (field (name "Manufacturer") "UNI-ROYAL(厚声)")
      )
      (libsource (lib "easyedapro") (part "电阻"))
    )
    (comp (ref "U19")
      (value "TPS5430DDAR")
      (footprint "easyedapro:ESOP-8_L4.9-W3.9-P1.27-LS6.0-TL-EP")
      (description "功能类型:降压型;输出类型:可调;输入电压:5.5V~36V;输出电压:1.221V~32.04V;输出电流(最大值):3A;")
      (fields (field (name "Manufacturer") "TI(德州仪器)"))
      (libsource (lib "easyedapro") (part "TPS5430DDAR"))
    )
  )
  (nets
    (net (code "1") (name "+5V") (class "Default")
      (node (ref "C20") (pin "1") (pinfunction "1_1") (pintype "input"))
      (node (ref "C75") (pin "2") (pinfunction "2_2") (pintype "input"))
      (node (ref "C9") (pin "2") (pinfunction "2_2") (pintype "input"))
      (node (ref "H25") (pin "1") (pinfunction "1_1") (pintype "unspecified"))
      (node (ref "H26") (pin "1") (pinfunction "1_1") (pintype "unspecified"))
      (node (ref "H27") (pin "1") (pinfunction "1_1") (pintype "unspecified"))
      (node (ref "H28") (pin "1") (pinfunction "1_1") (pintype "unspecified"))
      (node (ref "H29") (pin "1") (pinfunction "1_1") (pintype "unspecified"))
      (node (ref "H30") (pin "1") (pinfunction "1_1") (pintype "unspecified"))
      (node (ref "L2") (pin "1") (pinfunction "1_1") (pintype "unspecified"))
      (node (ref "R11") (pin "2") (pinfunction "2_2") (pintype "input"))
      (node (ref "R13") (pin "1") (pinfunction "1_1") (pintype "input"))
      (node (ref "R14") (pin "1") (pinfunction "1_1") (pintype "input"))
      (node (ref "R27") (pin "2") (pinfunction "2_2") (pintype "input"))
      (node (ref "R28") (pin "1") (pinfunction "1_1") (pintype "input"))
      (node (ref "R29") (pin "1") (pinfunction "1_1") (pintype "input"))
      (node (ref "R3") (pin "2") (pinfunction "2_2") (pintype "input"))
      (node (ref "R33") (pin "2") (pinfunction "2_2") (pintype "input"))
      (node (ref "R35") (pin "2") (pinfunction "2_2") (pintype "input"))
      (node (ref "R37") (pin "2") (pinfunction "2_2") (pintype "input"))
      (node (ref "R39") (pin "2") (pinfunction "2_2") (pintype "input"))
      (node (ref "R41") (pin "2") (pinfunction "2_2") (pintype "input"))
      (node (ref "R5") (pin "2") (pinfunction "2_2") (pintype "input"))
      (node (ref "R58") (pin "2") (pinfunction "2_2") (pintype "input"))
      (node (ref "R59") (pin "2") (pinfunction "2_2") (pintype "input"))
      (node (ref "R7") (pin "2") (pinfunction "2_2") (pintype "input"))
      (node (ref "R9") (pin "2") (pinfunction "2_2") (pintype "input"))
      (node (ref "U10") (pin "3") (pinfunction "VIN_3") (pintype "input"))
      (node (ref "U14") (pin "10") (pinfunction "VCC_10") (pintype "input"))
      (node (ref "U3") (pin "10") (pinfunction "VCC_10") (pintype "input"))
    )
    (net (code "2") (name "3.3V") (class "Default")
      (node (ref "C44") (pin "1") (pinfunction "1_1") (pintype "input"))
      (node (ref "C48") (pin "2") (pinfunction "2_2") (pintype "input"))
      (node (ref "C52") (pin "2") (pinfunction "2_2") (pintype "input"))
      (node (ref "C53") (pin "2") (pinfunction "2_2") (pintype "input"))
      (node (ref "C54") (pin "2") (pinfunction "2_2") (pintype "input"))
      (node (ref "C55") (pin "2") (pinfunction "2_2") (pintype "input"))
      (node (ref "C56") (pin "2") (pinfunction "2_2") (pintype "input"))
      (node (ref "C57") (pin "2") (pinfunction "2_2") (pintype "input"))
      (node (ref "C58") (pin "2") (pinfunction "2_2") (pintype "input"))
      (node (ref "C59") (pin "2") (pinfunction "2_2") (pintype "input"))
      (node (ref "C61") (pin "2") (pinfunction "2_2") (pintype "input"))
      (node (ref "C62") (pin "2") (pinfunction "2_2") (pintype "input"))
      (node (ref "C65") (pin "2") (pinfunction "2_2") (pintype "input"))
      (node (ref "C66") (pin "2") (pinfunction "2_2") (pintype "input"))
      (node (ref "C8") (pin "2") (pinfunction "2_2") (pintype "input"))
      (node (ref "H10") (pin "1") (pinfunction "1_1") (pintype "input"))
      (node (ref "R1") (pin "2") (pinfunction "2_2") (pintype "input"))
      (node (ref "R2") (pin "2") (pinfunction "2_2") (pintype "input"))
      (node (ref "R44") (pin "2") (pinfunction "2_2") (pintype "input"))
      (node (ref "R45") (pin "2") (pinfunction "2_2") (pintype "input"))
      (node (ref "R57") (pin "2") (pinfunction "2_2") (pintype "input"))
      (node (ref "R61") (pin "2") (pinfunction "2_2") (pintype "input"))
      (node (ref "U1") (pin "108") (pinfunction "VDD_108") (pintype "unspecified"))
      (node (ref "U1") (pin "121") (pinfunction "VDD_121") (pintype "unspecified"))
      (node (ref "U1") (pin "131") (pinfunction "VDD_131") (pintype "unspecified"))
      (node (ref "U1") (pin "143") (pinfunction "PDR_ON_143") (pintype "unspecified"))
      (node (ref "U1") (pin "144") (pinfunction "VDD_144") (pintype "unspecified"))
      (node (ref "U1") (pin "17") (pinfunction "VDD_17") (pintype "unspecified"))
      (node (ref "U1") (pin "30") (pinfunction "VDD_30") (pintype "unspecified"))
      (node (ref "U1") (pin "32") (pinfunction "VREF+_32") (pintype "unspecified"))
      (node (ref "U1") (pin "33") (pinfunction "VDDA_33") (pintype "unspecified"))
      (node (ref "U1") (pin "39") (pinfunction "VDD_39") (pintype "unspecified"))
      (node (ref "U1") (pin "52") (pinfunction "VDD_52") (pintype "unspecified"))
      (node (ref "U1") (pin "6") (pinfunction "VBAT_6") (pintype "unspecified"))
      (node (ref "U1") (pin "62") (pinfunction "VDD_62") (pintype "unspecified"))
      (node (ref "U1") (pin "72") (pinfunction "VDD_72") (pintype "unspecified"))
      (node (ref "U1") (pin "84") (pinfunction "VDD_84") (pintype "unspecified"))
      (node (ref "U1") (pin "95") (pinfunction "VDD_95") (pintype "unspecified"))
      (node (ref "U10") (pin "2") (pinfunction "VOUT_2") (pintype "input"))
      (node (ref "U28") (pin "13") (pinfunction "VDD_13") (pintype "input"))
      (node (ref "U28") (pin "8") (pinfunction "VLOGIC_8") (pintype "input"))
      (node (ref "c1") (pin "1") (pinfunction "1_1") (pintype "input"))
    )
    (net (code "3") (name "A0") (class "Default")
      (node (ref "R3") (pin "1") (pinfunction "1_1") (pintype "input"))
      (node (ref "R4") (pin "2") (pinfunction "2_2") (pintype "input"))
      (node (ref "U3") (pin "9") (pinfunction "A0_9") (pintype "input"))
    )
    (net (code "4") (name "A1") (class "Default")
      (node (ref "R5") (pin "1") (pinfunction "1_1") (pintype "input"))
      (node (ref "R6") (pin "2") (pinfunction "2_2") (pintype "input"))
      (node (ref "U3") (pin "8") (pinfunction "A1_8") (pintype "input"))
    )
    (net (code "5") (name "A2") (class "Default")
      (node (ref "R7") (pin "1") (pinfunction "1_1") (pintype "input"))
      (node (ref "R8") (pin "2") (pinfunction "2_2") (pintype "input"))
      (node (ref "U3") (pin "7") (pinfunction "A2_7") (pintype "input"))
    )
    (net (code "6") (name "A3") (class "Default")
      (node (ref "R10") (pin "2") (pinfunction "2_2") (pintype "input"))
      (node (ref "R9") (pin "1") (pinfunction "1_1") (pintype "input"))
      (node (ref "U3") (pin "6") (pinfunction "A3_6") (pintype "input"))
    )
    (net (code "7") (name "A4") (class "Default")
      (node (ref "R11") (pin "1") (pinfunction "1_1") (pintype "input"))
      (node (ref "R12") (pin "2") (pinfunction "2_2") (pintype "input"))
      (node (ref "U3") (pin "5") (pinfunction "A4_5") (pintype "input"))
    )
    (net (code "8") (name "A5") (class "Default")
      (node (ref "R33") (pin "1") (pinfunction "1_1") (pintype "input"))
      (node (ref "R34") (pin "2") (pinfunction "2_2") (pintype "input"))
      (node (ref "U14") (pin "9") (pinfunction "A0_9") (pintype "input"))
    )
    (net (code "9") (name "A6") (class "Default")
      (node (ref "R35") (pin "1") (pinfunction "1_1") (pintype "input"))
      (node (ref "R36") (pin "2") (pinfunction "2_2") (pintype "input"))
      (node (ref "U14") (pin "8") (pinfunction "A1_8") (pintype "input"))
    )
    (net (code "10") (name "A7") (class "Default")
      (node (ref "R37") (pin "1") (pinfunction "1_1") (pintype "input"))
      (node (ref "R38") (pin "2") (pinfunction "2_2") (pintype "input"))
      (node (ref "U14") (pin "7") (pinfunction "A2_7") (pintype "input"))
    )
    (net (code "11") (name "A8") (class "Default")
      (node (ref "R39") (pin "1") (pinfunction "1_1") (pintype "input"))
      (node (ref "R40") (pin "2") (pinfunction "2_2") (pintype "input"))
      (node (ref "U14") (pin "6") (pinfunction "A3_6") (pintype "input"))
    )
    (net (code "12") (name "A9") (class "Default")
      (node (ref "R41") (pin "1") (pinfunction "1_1") (pintype "input"))
      (node (ref "R42") (pin "2") (pinfunction "2_2") (pintype "input"))
      (node (ref "U14") (pin "5") (pinfunction "A4_5") (pintype "input"))
    )
    (net (code "13") (name "ADC1") (class "Default")
      (node (ref "C67") (pin "2") (pinfunction "2_2") (pintype "input"))
      (node (ref "H56") (pin "2") (pinfunction "2_2") (pintype "input"))
      (node (ref "R49") (pin "2") (pinfunction "2_2") (pintype "input"))
      (node (ref "U1") (pin "40") (pinfunction "PA4_40") (pintype "unspecified"))
    )
    (net (code "14") (name "ADC2") (class "Default")
      (node (ref "C68") (pin "2") (pinfunction "2_2") (pintype "input"))
      (node (ref "H55") (pin "2") (pinfunction "2_2") (pintype "input"))
      (node (ref "R50") (pin "2") (pinfunction "2_2") (pintype "input"))
      (node (ref "U1") (pin "41") (pinfunction "PA5_41") (pintype "unspecified"))
    )
    (net (code "15") (name "ADC3") (class "Default")
      (node (ref "C69") (pin "2") (pinfunction "2_2") (pintype "input"))
      (node (ref "H54") (pin "2") (pinfunction "2_2") (pintype "input"))
      (node (ref "R51") (pin "2") (pinfunction "2_2") (pintype "input"))
      (node (ref "U1") (pin "42") (pinfunction "PA6_42") (pintype "unspecified"))
    )
    (net (code "16") (name "ADC4") (class "Default")
      (node (ref "C70") (pin "2") (pinfunction "2_2") (pintype "input"))
      (node (ref "H53") (pin "2") (pinfunction "2_2") (pintype "input"))
      (node (ref "R52") (pin "2") (pinfunction "2_2") (pintype "input"))
      (node (ref "U1") (pin "43") (pinfunction "PA7_43") (pintype "unspecified"))
    )
    (net (code "17") (name "ADC5") (class "Default")
      (node (ref "C71") (pin "2") (pinfunction "2_2") (pintype "input"))
      (node (ref "H52") (pin "2") (pinfunction "2_2") (pintype "input"))
      (node (ref "R53") (pin "2") (pinfunction "2_2") (pintype "input"))
      (node (ref "U1") (pin "44") (pinfunction "PC4_44") (pintype "unspecified"))
    )
    (net (code "18") (name "ADC6") (class "Default")
      (node (ref "C72") (pin "2") (pinfunction "2_2") (pintype "input"))
      (node (ref "H51") (pin "2") (pinfunction "2_2") (pintype "input"))
      (node (ref "R54") (pin "2") (pinfunction "2_2") (pintype "input"))
      (node (ref "U1") (pin "45") (pinfunction "PC5_45") (pintype "unspecified"))
    )
    (net (code "19") (name "ADC7") (class "Default")
      (node (ref "C73") (pin "2") (pinfunction "2_2") (pintype "input"))
      (node (ref "H50") (pin "2") (pinfunction "2_2") (pintype "input"))
      (node (ref "R55") (pin "2") (pinfunction "2_2") (pintype "input"))
      (node (ref "U1") (pin "46") (pinfunction "PB0_46") (pintype "unspecified"))
    )
    (net (code "20") (name "ADC8") (class "Default")
      (node (ref "C74") (pin "2") (pinfunction "2_2") (pintype "input"))
      (node (ref "H49") (pin "2") (pinfunction "2_2") (pintype "input"))
      (node (ref "R56") (pin "2") (pinfunction "2_2") (pintype "input"))
      (node (ref "U1") (pin "47") (pinfunction "PB1_47") (pintype "unspecified"))
    )
    (net (code "21") (name "ADC_VCC") (class "Default")
      (node (ref "H49") (pin "1") (pinfunction "1_1") (pintype "input"))
      (node (ref "H50") (pin "1") (pinfunction "1_1") (pintype "input"))
      (node (ref "H51") (pin "1") (pinfunction "1_1") (pintype "input"))
      (node (ref "H52") (pin "1") (pinfunction "1_1") (pintype "input"))
      (node (ref "H53") (pin "1") (pinfunction "1_1") (pintype "input"))
      (node (ref "H54") (pin "1") (pinfunction "1_1") (pintype "input"))
      (node (ref "H55") (pin "1") (pinfunction "1_1") (pintype "input"))
      (node (ref "H56") (pin "1") (pinfunction "1_1") (pintype "input"))
      (node (ref "H76") (pin "1") (pinfunction "1_1") (pintype "input"))
      (node (ref "H77") (pin "1") (pinfunction "1_1") (pintype "input"))
      (node (ref "H79") (pin "1") (pinfunction "1_1") (pintype "input"))
      (node (ref "H82") (pin "1") (pinfunction "1_1") (pintype "input"))
      (node (ref "H83") (pin "1") (pinfunction "1_1") (pintype "input"))
      (node (ref "H84") (pin "1") (pinfunction "1_1") (pintype "input"))
      (node (ref "R57") (pin "1") (pinfunction "1_1") (pintype "input"))
      (node (ref "R58") (pin "1") (pinfunction "1_1") (pintype "input"))
    )
    (net (code "22") (name "CLK") (class "Default")
      (node (ref "H10") (pin "4") (pinfunction "4_4") (pintype "input"))
      (node (ref "U1") (pin "109") (pinfunction "PA14_109") (pintype "unspecified"))
    )
    (net (code "23") (name "DIO") (class "Default")
      (node (ref "H10") (pin "3") (pinfunction "3_3") (pintype "input"))
      (node (ref "U1") (pin "105") (pinfunction "PA13_105") (pintype "unspecified"))
    )
    (net (code "24") (name "DJ0") (class "Default")
      (node (ref "H57") (pin "1") (pinfunction "1_1") (pintype "unspecified"))
      (node (ref "U3") (pin "17") (pinfunction "DJ0_17") (pintype "input"))
    )
    (net (code "25") (name "DJ1") (class "Default")
      (node (ref "H58") (pin "1") (pinfunction "1_1") (pintype "unspecified"))
      (node (ref "U3") (pin "18") (pinfunction "DJ1_18") (pintype "input"))
    )
    (net (code "26") (name "DJ2") (class "Default")
      (node (ref "H59") (pin "1") (pinfunction "1_1") (pintype "unspecified"))
      (node (ref "U3") (pin "19") (pinfunction "DJ2_19") (pintype "input"))
    )
    (net (code "27") (name "DJ3") (class "Default")
      (node (ref "H60") (pin "1") (pinfunction "1_1") (pintype "unspecified"))
      (node (ref "U3") (pin "20") (pinfunction "DJ3_20") (pintype "input"))
    )
    (net (code "28") (name "DJ4") (class "Default")
      (node (ref "H61") (pin "1") (pinfunction "1_1") (pintype "unspecified"))
      (node (ref "U3") (pin "21") (pinfunction "DJ4_21") (pintype "input"))
    )
    (net (code "29") (name "DJ5") (class "Default")
      (node (ref "H62") (pin "1") (pinfunction "1_1") (pintype "unspecified"))
      (node (ref "U3") (pin "22") (pinfunction "DJ5_22") (pintype "input"))
    )
    (net (code "30") (name "DJ6") (class "Default")
      (node (ref "H64") (pin "1") (pinfunction "1_1") (pintype "unspecified"))
      (node (ref "U3") (pin "23") (pinfunction "DJ6_23") (pintype "input"))
    )
    (net (code "31") (name "DJ7") (class "Default")
      (node (ref "H65") (pin "1") (pinfunction "1_1") (pintype "unspecified"))
      (node (ref "U3") (pin "24") (pinfunction "DJ7_24") (pintype "input"))
    )
    (net (code "32") (name "DJ8") (class "Default")
      (node (ref "H66") (pin "1") (pinfunction "1_1") (pintype "unspecified"))
      (node (ref "U3") (pin "25") (pinfunction "DJ8_25") (pintype "input"))
    )
    (net (code "33") (name "DJ9") (class "Default")
      (node (ref "H67") (pin "1") (pinfunction "1_1") (pintype "unspecified"))
      (node (ref "U14") (pin "17") (pinfunction "DJ0_17") (pintype "input"))
    )
    (net (code "34") (name "DJ10") (class "Default")
      (node (ref "H68") (pin "1") (pinfunction "1_1") (pintype "unspecified"))
      (node (ref "U14") (pin "18") (pinfunction "DJ1_18") (pintype "input"))
    )
    (net (code "35") (name "DJ11") (class "Default")
      (node (ref "H69") (pin "1") (pinfunction "1_1") (pintype "unspecified"))
      (node (ref "U14") (pin "19") (pinfunction "DJ2_19") (pintype "input"))
    )
    (net (code "36") (name "DJ12") (class "Default")
      (node (ref "H70") (pin "1") (pinfunction "1_1") (pintype "unspecified"))
      (node (ref "U14") (pin "20") (pinfunction "DJ3_20") (pintype "input"))
    )
    (net (code "37") (name "DJ13") (class "Default")
      (node (ref "H71") (pin "1") (pinfunction "1_1") (pintype "unspecified"))
      (node (ref "U14") (pin "21") (pinfunction "DJ4_21") (pintype "input"))
    )
    (net (code "38") (name "DJ14") (class "Default")
      (node (ref "H72") (pin "1") (pinfunction "1_1") (pintype "unspecified"))
      (node (ref "U14") (pin "22") (pinfunction "DJ5_22") (pintype "input"))
    )
    (net (code "39") (name "DJ15") (class "Default")
      (node (ref "H73") (pin "1") (pinfunction "1_1") (pintype "unspecified"))
      (node (ref "U14") (pin "23") (pinfunction "DJ6_23") (pintype "input"))
    )
    (net (code "40") (name "DJ16") (class "Default")
      (node (ref "H74") (pin "1") (pinfunction "1_1") (pintype "unspecified"))
      (node (ref "U14") (pin "24") (pinfunction "DJ7_24") (pintype "input"))
    )
    (net (code "41") (name "DJ17") (class "Default")
      (node (ref "H75") (pin "1") (pinfunction "1_1") (pintype "unspecified"))
      (node (ref "U14") (pin "25") (pinfunction "DJ8_25") (pintype "input"))
    )
    (net (code "42") (name "GND") (class "Default")
      (node (ref "C1") (pin "1") (pinfunction "1_1") (pintype "input"))
      (node (ref "C20") (pin "2") (pinfunction "2_2") (pintype "input"))
      (node (ref "C25") (pin "2") (pinfunction "2_2") (pintype "input"))
      (node (ref "C44") (pin "2") (pinfunction "2_2") (pintype "input"))
      (node (ref "C48") (pin "1") (pinfunction "1_1") (pintype "input"))
      (node (ref "C49") (pin "1") (pinfunction "1_1") (pintype "input"))
      (node (ref "C50") (pin "2") (pinfunction "2_2") (pintype "input"))
      (node (ref "C52") (pin "1") (pinfunction "1_1") (pintype "input"))
      (node (ref "C53") (pin "1") (pinfunction "1_1") (pintype "input"))
      (node (ref "C54") (pin "1") (pinfunction "1_1") (pintype "input"))
      (node (ref "C55") (pin "1") (pinfunction "1_1") (pintype "input"))
      (node (ref "C56") (pin "1") (pinfunction "1_1") (pintype "input"))
      (node (ref "C57") (pin "1") (pinfunction "1_1") (pintype "input"))
      (node (ref "C58") (pin "1") (pinfunction "1_1") (pintype "input"))
      (node (ref "C59") (pin "1") (pinfunction "1_1") (pintype "input"))
      (node (ref "C61") (pin "1") (pinfunction "1_1") (pintype "input"))
      (node (ref "C62") (pin "1") (pinfunction "1_1") (pintype "input"))
      (node (ref "C65") (pin "1") (pinfunction "1_1") (pintype "input"))
      (node (ref "C66") (pin "1") (pinfunction "1_1") (pintype "input"))
      (node (ref "C67") (pin "1") (pinfunction "1_1") (pintype "input"))
      (node (ref "C68") (pin "1") (pinfunction "1_1") (pintype "input"))
      (node (ref "C69") (pin "1") (pinfunction "1_1") (pintype "input"))
      (node (ref "C70") (pin "1") (pinfunction "1_1") (pintype "input"))
      (node (ref "C71") (pin "1") (pinfunction "1_1") (pintype "input"))
      (node (ref "C72") (pin "1") (pinfunction "1_1") (pintype "input"))
      (node (ref "C73") (pin "1") (pinfunction "1_1") (pintype "input"))
      (node (ref "C74") (pin "1") (pinfunction "1_1") (pintype "input"))
      (node (ref "C75") (pin "1") (pinfunction "1_1") (pintype "input"))
      (node (ref "C76") (pin "1") (pinfunction "1_1") (pintype "input"))
      (node (ref "C77") (pin "1") (pinfunction "1_1") (pintype "input"))
      (node (ref "C8") (pin "1") (pinfunction "1_1") (pintype "input"))
      (node (ref "C9") (pin "1") (pinfunction "1_1") (pintype "input"))
      (node (ref "D15") (pin "2") (pinfunction "A_2") (pintype "unspecified"))
      (node (ref "H10") (pin "2") (pinfunction "2_2") (pintype "input"))
      (node (ref "H25") (pin "4") (pinfunction "4_4") (pintype "unspecified"))
      (node (ref "H26") (pin "4") (pinfunction "4_4") (pintype "unspecified"))
      (node (ref "H27") (pin "4") (pinfunction "4_4") (pintype "unspecified"))
      (node (ref "H28") (pin "4") (pinfunction "4_4") (pintype "unspecified"))
      (node (ref "H29") (pin "4") (pinfunction "4_4") (pintype "unspecified"))
      (node (ref "H30") (pin "4") (pinfunction "4_4") (pintype "unspecified"))
      (node (ref "H76") (pin "2") (pinfunction "2_2") (pintype "input"))
      (node (ref "H77") (pin "2") (pinfunction "2_2") (pintype "input"))
      (node (ref "H79") (pin "2") (pinfunction "2_2") (pintype "input"))
      (node (ref "H82") (pin "2") (pinfunction "2_2") (pintype "input"))
      (node (ref "H83") (pin "2") (pinfunction "2_2") (pintype "input"))
      (node (ref "H84") (pin "2") (pinfunction "2_2") (pintype "input"))
      (node (ref "LED1") (pin "1") (pinfunction "C_1") (pintype "input"))
      (node (ref "P1") (pin "2") (pinfunction "2_2") (pintype "unspecified"))
      (node (ref "R10") (pin "1") (pinfunction "1_1") (pintype "input"))
      (node (ref "R12") (pin "1") (pinfunction "1_1") (pintype "input"))
      (node (ref "R17") (pin "2") (pinfunction "2_2") (pintype "input"))
      (node (ref "R26") (pin "1") (pinfunction "1_1") (pintype "input"))
      (node (ref "R32") (pin "2") (pinfunction "2_2") (pintype "input"))
      (node (ref "R34") (pin "1") (pinfunction "1_1") (pintype "input"))
      (node (ref "R36") (pin "1") (pinfunction "1_1") (pintype "input"))
      (node (ref "R38") (pin "1") (pinfunction "1_1") (pintype "input"))
      (node (ref "R4") (pin "1") (pinfunction "1_1") (pintype "input"))
      (node (ref "R40") (pin "1") (pinfunction "1_1") (pintype "input"))
      (node (ref "R42") (pin "1") (pinfunction "1_1") (pintype "input"))
      (node (ref "R43") (pin "1") (pinfunction "1_1") (pintype "input"))
      (node (ref "R46") (pin "2") (pinfunction "2_2") (pintype "input"))
      (node (ref "R49") (pin "1") (pinfunction "1_1") (pintype "input"))
      (node (ref "R50") (pin "1") (pinfunction "1_1") (pintype "input"))
      (node (ref "R51") (pin "1") (pinfunction "1_1") (pintype "input"))
      (node (ref "R52") (pin "1") (pinfunction "1_1") (pintype "input"))
      (node (ref "R53") (pin "1") (pinfunction "1_1") (pintype "input"))
      (node (ref "R54") (pin "1") (pinfunction "1_1") (pintype "input"))
      (node (ref "R55") (pin "1") (pinfunction "1_1") (pintype "input"))
      (node (ref "R56") (pin "1") (pinfunction "1_1") (pintype "input"))
      (node (ref "R6") (pin "1") (pinfunction "1_1") (pintype "input"))
      (node (ref "R8") (pin "1") (pinfunction "1_1") (pintype "input"))
      (node (ref "U1") (pin "107") (pinfunction "VSS_107") (pintype "unspecified"))
      (node (ref "U1") (pin "120") (pinfunction "VSS_120") (pintype "unspecified"))
      (node (ref "U1") (pin "130") (pinfunction "VSS_130") (pintype "unspecified"))
      (node (ref "U1") (pin "16") (pinfunction "VSS_16") (pintype "unspecified"))
      (node (ref "U1") (pin "31") (pinfunction "VSSA_31") (pintype "unspecified"))
      (node (ref "U1") (pin "38") (pinfunction "VSS_38") (pintype "unspecified"))
      (node (ref "U1") (pin "51") (pinfunction "VSS_51") (pintype "unspecified"))
      (node (ref "U1") (pin "61") (pinfunction "VSS_61") (pintype "unspecified"))
      (node (ref "U1") (pin "83") (pinfunction "VSS_83") (pintype "unspecified"))
      (node (ref "U1") (pin "94") (pinfunction "VSS_94") (pintype "unspecified"))
      (node (ref "U10") (pin "1") (pinfunction "VSS_1") (pintype "input"))
      (node (ref "U14") (pin "11") (pinfunction "GND_11") (pintype "input"))
      (node (ref "U14") (pin "12") (pinfunction "GND_12") (pintype "input"))
      (node (ref "U19") (pin "6") (pinfunction "GND_6") (pintype "unspecified"))
      (node (ref "U19") (pin "9") (pinfunction "PowerPAD_9") (pintype "unspecified"))
      (node (ref "U28") (pin "1") (pinfunction "CLKIN_1") (pintype "input"))
      (node (ref "U28") (pin "11") (pinfunction "FSYNC_11") (pintype "input"))
      (node (ref "U28") (pin "18") (pinfunction "GND_18") (pintype "input"))
      (node (ref "U28") (pin "25") (pinfunction "EP_25") (pintype "input"))
      (node (ref "U3") (pin "11") (pinfunction "GND_11") (pintype "input"))
      (node (ref "U3") (pin "12") (pinfunction "GND_12") (pintype "input"))
      (node (ref "c0") (pin "2") (pinfunction "2_2") (pintype "input"))
      (node (ref "c1") (pin "2") (pinfunction "2_2") (pintype "input"))
      (node (ref "c3") (pin "1") (pinfunction "1_1") (pintype "input"))
    )
    (net (code "43") (name "LED") (class "Default")
      (node (ref "LED3") (pin "1") (pinfunction "C_1") (pintype "input"))
      (node (ref "U1") (pin "110") (pinfunction "PA15_110") (pintype "unspecified"))
    )
    (net (code "44") (name "NRST") (class "Default")
      (node (ref "C1") (pin "2") (pinfunction "2_2") (pintype "input"))
      (node (ref "H10") (pin "5") (pinfunction "5_5") (pintype "input"))
      (node (ref "R2") (pin "1") (pinfunction "1_1") (pintype "input"))
      (node (ref "U1") (pin "25") (pinfunction "NRST_25") (pintype "unspecified"))
    )
    (net (code "45") (name "Net-(D15-K)") (class "Default")
      (node (ref "C40") (pin "2") (pinfunction "2_2") (pintype "input"))
      (node (ref "D15") (pin "1") (pinfunction "K_1") (pintype "unspecified"))
      (node (ref "L2") (pin "2") (pinfunction "2_2") (pintype "unspecified"))
      (node (ref "U19") (pin "8") (pinfunction "PH_8") (pintype "unspecified"))
    )
    (net (code "46") (name "Net-(LED1-A)") (class "Default")
      (node (ref "LED1") (pin "2") (pinfunction "A_2") (pintype "input"))
      (node (ref "R59") (pin "1") (pinfunction "1_1") (pintype "input"))
    )
    (net (code "47") (name "Net-(LED3-A)") (class "Default")
      (node (ref "LED3") (pin "2") (pinfunction "A_2") (pintype "input"))
      (node (ref "R61") (pin "1") (pinfunction "1_1") (pintype "input"))
    )
    (net (code "48") (name "Net-(U1-BOOT0)") (class "Default")
      (node (ref "R43") (pin "2") (pinfunction "2_2") (pintype "input"))
      (node (ref "U1") (pin "138") (pinfunction "BOOT0_138") (pintype "unspecified"))
    )
    (net (code "49") (name "Net-(U1-VCAP_1)") (class "Default")
      (node (ref "C50") (pin "1") (pinfunction "1_1") (pintype "input"))
      (node (ref "U1") (pin "71") (pinfunction "VCAP_1_71") (pintype "unspecified"))
    )
    (net (code "50") (name "Net-(U1-VCAP_2)") (class "Default")
      (node (ref "C49") (pin "2") (pinfunction "2_2") (pintype "input"))
      (node (ref "U1") (pin "106") (pinfunction "VCAP_2_106") (pintype "unspecified"))
    )
    (net (code "51") (name "Net-(U3-SCL)") (class "Default")
      (node (ref "R14") (pin "2") (pinfunction "2_2") (pintype "input"))
      (node (ref "R16") (pin "2") (pinfunction "2_2") (pintype "input"))
      (node (ref "U3") (pin "15") (pinfunction "SCL_15") (pintype "input"))
    )
    (net (code "52") (name "Net-(U3-SDA)") (class "Default")
      (node (ref "R13") (pin "2") (pinfunction "2_2") (pintype "input"))
      (node (ref "R15") (pin "2") (pinfunction "2_2") (pintype "input"))
      (node (ref "U3") (pin "16") (pinfunction "SDA_16") (pintype "input"))
    )
    (net (code "53") (name "Net-(U14-SCL)") (class "Default")
      (node (ref "R29") (pin "2") (pinfunction "2_2") (pintype "input"))
      (node (ref "R31") (pin "2") (pinfunction "2_2") (pintype "input"))
      (node (ref "U14") (pin "15") (pinfunction "SCL_15") (pintype "input"))
    )
    (net (code "54") (name "Net-(U14-SDA)") (class "Default")
      (node (ref "R28") (pin "2") (pinfunction "2_2") (pintype "input"))
      (node (ref "R30") (pin "2") (pinfunction "2_2") (pintype "input"))
      (node (ref "U14") (pin "16") (pinfunction "SDA_16") (pintype "input"))
    )
    (net (code "55") (name "Net-(U19-BOOT)") (class "Default")
      (node (ref "C40") (pin "1") (pinfunction "1_1") (pintype "input"))
      (node (ref "U19") (pin "1") (pinfunction "BOOT_1") (pintype "unspecified"))
    )
    (net (code "56") (name "Net-(U19-VSENSE)") (class "Default")
      (node (ref "R26") (pin "2") (pinfunction "2_2") (pintype "input"))
      (node (ref "R27") (pin "1") (pinfunction "1_1") (pintype "input"))
      (node (ref "U19") (pin "4") (pinfunction "VSENSE_4") (pintype "unspecified"))
    )
    (net (code "57") (name "Net-(U28-AD0)") (class "Default")
      (node (ref "R45") (pin "1") (pinfunction "1_1") (pintype "input"))
      (node (ref "R46") (pin "1") (pinfunction "1_1") (pintype "input"))
      (node (ref "U28") (pin "9") (pinfunction "AD0_9") (pintype "input"))
    )
    (net (code "58") (name "Net-(U28-CPOUT)") (class "Default")
      (node (ref "U28") (pin "20") (pinfunction "CPOUT_20") (pintype "input"))
      (node (ref "c0") (pin "1") (pinfunction "1_1") (pintype "input"))
    )
    (net (code "59") (name "Net-(U28-REGOUT)") (class "Default")
      (node (ref "U28") (pin "10") (pinfunction "REGOUT_10") (pintype "input"))
      (node (ref "c3") (pin "2") (pinfunction "2_2") (pintype "input"))
    )
    (net (code "60") (name "PGND") (class "Default")
      (node (ref "H57") (pin "3") (pinfunction "3_3") (pintype "unspecified"))
      (node (ref "H58") (pin "3") (pinfunction "3_3") (pintype "unspecified"))
      (node (ref "H59") (pin "3") (pinfunction "3_3") (pintype "unspecified"))
      (node (ref "H60") (pin "3") (pinfunction "3_3") (pintype "unspecified"))
      (node (ref "H61") (pin "3") (pinfunction "3_3") (pintype "unspecified"))
      (node (ref "H62") (pin "3") (pinfunction "3_3") (pintype "unspecified"))
      (node (ref "H64") (pin "3") (pinfunction "3_3") (pintype "unspecified"))
      (node (ref "H65") (pin "3") (pinfunction "3_3") (pintype "unspecified"))
      (node (ref "H66") (pin "3") (pinfunction "3_3") (pintype "unspecified"))
      (node (ref "H67") (pin "3") (pinfunction "3_3") (pintype "unspecified"))
      (node (ref "H68") (pin "3") (pinfunction "3_3") (pintype "unspecified"))
      (node (ref "H69") (pin "3") (pinfunction "3_3") (pintype "unspecified"))
      (node (ref "H70") (pin "3") (pinfunction "3_3") (pintype "unspecified"))
      (node (ref "H71") (pin "3") (pinfunction "3_3") (pintype "unspecified"))
      (node (ref "H72") (pin "3") (pinfunction "3_3") (pintype "unspecified"))
      (node (ref "H73") (pin "3") (pinfunction "3_3") (pintype "unspecified"))
      (node (ref "H74") (pin "3") (pinfunction "3_3") (pintype "unspecified"))
      (node (ref "H75") (pin "3") (pinfunction "3_3") (pintype "unspecified"))
      (node (ref "R17") (pin "1") (pinfunction "1_1") (pintype "input"))
      (node (ref "R32") (pin "1") (pinfunction "1_1") (pintype "input"))
    )
    (net (code "61") (name "SCL1") (class "Default")
      (node (ref "R16") (pin "1") (pinfunction "1_1") (pintype "input"))
      (node (ref "U1") (pin "136") (pinfunction "PB6_136") (pintype "unspecified"))
    )
    (net (code "62") (name "SCL2") (class "Default")
      (node (ref "R31") (pin "1") (pinfunction "1_1") (pintype "input"))
      (node (ref "U1") (pin "11") (pinfunction "PF1_11") (pintype "unspecified"))
    )
    (net (code "63") (name "SCL3") (class "Default")
      (node (ref "R44") (pin "1") (pinfunction "1_1") (pintype "input"))
      (node (ref "U1") (pin "100") (pinfunction "PA8_100") (pintype "unspecified"))
      (node (ref "U28") (pin "23") (pinfunction "SCL_23") (pintype "input"))
    )
    (net (code "64") (name "SDA1") (class "Default")
      (node (ref "R15") (pin "1") (pinfunction "1_1") (pintype "input"))
      (node (ref "U1") (pin "137") (pinfunction "PB7_137") (pintype "unspecified"))
    )
    (net (code "65") (name "SDA2") (class "Default")
      (node (ref "R30") (pin "1") (pinfunction "1_1") (pintype "input"))
      (node (ref "U1") (pin "10") (pinfunction "PF0_10") (pintype "unspecified"))
    )
    (net (code "66") (name "SDA3") (class "Default")
      (node (ref "R1") (pin "1") (pinfunction "1_1") (pintype "input"))
      (node (ref "U1") (pin "99") (pinfunction "PC9_99") (pintype "unspecified"))
      (node (ref "U28") (pin "24") (pinfunction "SDA_24") (pintype "input"))
    )
    (net (code "67") (name "UART4_RX") (class "Default")
      (node (ref "H28") (pin "3") (pinfunction "3_3") (pintype "unspecified"))
      (node (ref "U1") (pin "35") (pinfunction "PA1_35") (pintype "unspecified"))
    )
    (net (code "68") (name "UART4_TX") (class "Default")
      (node (ref "H28") (pin "2") (pinfunction "2_2") (pintype "unspecified"))
      (node (ref "U1") (pin "34") (pinfunction "PA0_34") (pintype "unspecified"))
    )
    (net (code "69") (name "UART5_RX") (class "Default")
      (node (ref "H29") (pin "2") (pinfunction "2_2") (pintype "unspecified"))
      (node (ref "U1") (pin "116") (pinfunction "PD2_116") (pintype "unspecified"))
    )
    (net (code "70") (name "UART5_TX") (class "Default")
      (node (ref "H29") (pin "3") (pinfunction "3_3") (pintype "unspecified"))
      (node (ref "U1") (pin "113") (pinfunction "PC12_113") (pintype "unspecified"))
    )
    (net (code "71") (name "USART1_RX") (class "Default")
      (node (ref "H25") (pin "2") (pinfunction "2_2") (pintype "unspecified"))
      (node (ref "U1") (pin "102") (pinfunction "PA10_102") (pintype "unspecified"))
    )
    (net (code "72") (name "USART1_TX") (class "Default")
      (node (ref "H25") (pin "3") (pinfunction "3_3") (pintype "unspecified"))
      (node (ref "U1") (pin "101") (pinfunction "PA9_101") (pintype "unspecified"))
    )
    (net (code "73") (name "USART2_RX") (class "Default")
      (node (ref "H26") (pin "3") (pinfunction "3_3") (pintype "unspecified"))
      (node (ref "U1") (pin "37") (pinfunction "PA3_37") (pintype "unspecified"))
    )
    (net (code "74") (name "USART2_TX") (class "Default")
      (node (ref "H26") (pin "2") (pinfunction "2_2") (pintype "unspecified"))
      (node (ref "U1") (pin "36") (pinfunction "PA2_36") (pintype "unspecified"))
    )
    (net (code "75") (name "USART3_RX") (class "Default")
      (node (ref "H27") (pin "3") (pinfunction "3_3") (pintype "unspecified"))
      (node (ref "U1") (pin "70") (pinfunction "PB11_70") (pintype "unspecified"))
    )
    (net (code "76") (name "USART3_TX") (class "Default")
      (node (ref "H27") (pin "2") (pinfunction "2_2") (pintype "unspecified"))
      (node (ref "U1") (pin "69") (pinfunction "PB10_69") (pintype "unspecified"))
    )
    (net (code "77") (name "USART6_RX") (class "Default")
      (node (ref "H30") (pin "2") (pinfunction "2_2") (pintype "unspecified"))
      (node (ref "U1") (pin "97") (pinfunction "PC7_97") (pintype "unspecified"))
    )
    (net (code "78") (name "USART6_TX") (class "Default")
      (node (ref "H30") (pin "3") (pinfunction "3_3") (pintype "unspecified"))
      (node (ref "U1") (pin "96") (pinfunction "PC6_96") (pintype "unspecified"))
    )
    (net (code "79") (name "VIN") (class "Default")
      (node (ref "C25") (pin "1") (pinfunction "1_1") (pintype "input"))
      (node (ref "C76") (pin "2") (pinfunction "2_2") (pintype "input"))
      (node (ref "C77") (pin "2") (pinfunction "2_2") (pintype "input"))
      (node (ref "H57") (pin "2") (pinfunction "2_2") (pintype "unspecified"))
      (node (ref "H58") (pin "2") (pinfunction "2_2") (pintype "unspecified"))
      (node (ref "H59") (pin "2") (pinfunction "2_2") (pintype "unspecified"))
      (node (ref "H60") (pin "2") (pinfunction "2_2") (pintype "unspecified"))
      (node (ref "H61") (pin "2") (pinfunction "2_2") (pintype "unspecified"))
      (node (ref "H62") (pin "2") (pinfunction "2_2") (pintype "unspecified"))
      (node (ref "H64") (pin "2") (pinfunction "2_2") (pintype "unspecified"))
      (node (ref "H65") (pin "2") (pinfunction "2_2") (pintype "unspecified"))
      (node (ref "H66") (pin "2") (pinfunction "2_2") (pintype "unspecified"))
      (node (ref "H67") (pin "2") (pinfunction "2_2") (pintype "unspecified"))
      (node (ref "H68") (pin "2") (pinfunction "2_2") (pintype "unspecified"))
      (node (ref "H69") (pin "2") (pinfunction "2_2") (pintype "unspecified"))
      (node (ref "H70") (pin "2") (pinfunction "2_2") (pintype "unspecified"))
      (node (ref "H71") (pin "2") (pinfunction "2_2") (pintype "unspecified"))
      (node (ref "H72") (pin "2") (pinfunction "2_2") (pintype "unspecified"))
      (node (ref "H73") (pin "2") (pinfunction "2_2") (pintype "unspecified"))
      (node (ref "H74") (pin "2") (pinfunction "2_2") (pintype "unspecified"))
      (node (ref "H75") (pin "2") (pinfunction "2_2") (pintype "unspecified"))
      (node (ref "P1") (pin "1") (pinfunction "1_1") (pintype "unspecified"))
      (node (ref "U19") (pin "7") (pinfunction "VIN_7") (pintype "unspecified"))
    )
    (net (code "80") (name "unconnected-(U1-PA11-Pad103)") (class "Default")
      (node (ref "U1") (pin "103") (pinfunction "PA11_103") (pintype "unspecified"))
    )
    (net (code "81") (name "unconnected-(U1-PA12-Pad104)") (class "Default")
      (node (ref "U1") (pin "104") (pinfunction "PA12_104") (pintype "unspecified"))
    )
    (net (code "82") (name "unconnected-(U1-PB2-Pad48)") (class "Default")
      (node (ref "U1") (pin "48") (pinfunction "PB2_48") (pintype "unspecified"))
    )
    (net (code "83") (name "unconnected-(U1-PB3-Pad133)") (class "Default")
      (node (ref "U1") (pin "133") (pinfunction "PB3_133") (pintype "unspecified"))
    )
    (net (code "84") (name "unconnected-(U1-PB4-Pad134)") (class "Default")
      (node (ref "U1") (pin "134") (pinfunction "PB4_134") (pintype "unspecified"))
    )
    (net (code "85") (name "unconnected-(U1-PB5-Pad135)") (class "Default")
      (node (ref "U1") (pin "135") (pinfunction "PB5_135") (pintype "unspecified"))
    )
    (net (code "86") (name "unconnected-(U1-PB8-Pad139)") (class "Default")
      (node (ref "U1") (pin "139") (pinfunction "PB8_139") (pintype "unspecified"))
    )
    (net (code "87") (name "unconnected-(U1-PB9-Pad140)") (class "Default")
      (node (ref "U1") (pin "140") (pinfunction "PB9_140") (pintype "unspecified"))
    )
    (net (code "88") (name "unconnected-(U1-PB12-Pad73)") (class "Default")
      (node (ref "U1") (pin "73") (pinfunction "PB12_73") (pintype "unspecified"))
    )
    (net (code "89") (name "unconnected-(U1-PB13-Pad74)") (class "Default")
      (node (ref "U1") (pin "74") (pinfunction "PB13_74") (pintype "unspecified"))
    )
    (net (code "90") (name "unconnected-(U1-PB14-Pad75)") (class "Default")
      (node (ref "U1") (pin "75") (pinfunction "PB14_75") (pintype "unspecified"))
    )
    (net (code "91") (name "unconnected-(U1-PB15-Pad76)") (class "Default")
      (node (ref "U1") (pin "76") (pinfunction "PB15_76") (pintype "unspecified"))
    )
    (net (code "92") (name "unconnected-(U1-PC0-Pad26)") (class "Default")
      (node (ref "U1") (pin "26") (pinfunction "PC0_26") (pintype "unspecified"))
    )
    (net (code "93") (name "unconnected-(U1-PC1-Pad27)") (class "Default")
      (node (ref "U1") (pin "27") (pinfunction "PC1_27") (pintype "unspecified"))
    )
    (net (code "94") (name "unconnected-(U1-PC2-Pad28)") (class "Default")
      (node (ref "U1") (pin "28") (pinfunction "PC2_28") (pintype "unspecified"))
    )
    (net (code "95") (name "unconnected-(U1-PC3-Pad29)") (class "Default")
      (node (ref "U1") (pin "29") (pinfunction "PC3_29") (pintype "unspecified"))
    )
    (net (code "96") (name "unconnected-(U1-PC8-Pad98)") (class "Default")
      (node (ref "U1") (pin "98") (pinfunction "PC8_98") (pintype "unspecified"))
    )
    (net (code "97") (name "unconnected-(U1-PC10-Pad111)") (class "Default")
      (node (ref "U1") (pin "111") (pinfunction "PC10_111") (pintype "unspecified"))
    )
    (net (code "98") (name "unconnected-(U1-PC11-Pad112)") (class "Default")
      (node (ref "U1") (pin "112") (pinfunction "PC11_112") (pintype "unspecified"))
    )
    (net (code "99") (name "unconnected-(U1-PC13-Pad7)") (class "Default")
      (node (ref "U1") (pin "7") (pinfunction "PC13_7") (pintype "unspecified"))
    )
    (net (code "100") (name "unconnected-(U1-PC14-Pad8)") (class "Default")
      (node (ref "U1") (pin "8") (pinfunction "PC14_8") (pintype "unspecified"))
    )
    (net (code "101") (name "unconnected-(U1-PC15-Pad9)") (class "Default")
      (node (ref "U1") (pin "9") (pinfunction "PC15_9") (pintype "unspecified"))
    )
    (net (code "102") (name "unconnected-(U1-PD0-Pad114)") (class "Default")
      (node (ref "U1") (pin "114") (pinfunction "PD0_114") (pintype "unspecified"))
    )
    (net (code "103") (name "unconnected-(U1-PD1-Pad115)") (class "Default")
      (node (ref "U1") (pin "115") (pinfunction "PD1_115") (pintype "unspecified"))
    )
    (net (code "104") (name "unconnected-(U1-PD3-Pad117)") (class "Default")
      (node (ref "U1") (pin "117") (pinfunction "PD3_117") (pintype "unspecified"))
    )
    (net (code "105") (name "unconnected-(U1-PD4-Pad118)") (class "Default")
      (node (ref "U1") (pin "118") (pinfunction "PD4_118") (pintype "unspecified"))
    )
    (net (code "106") (name "unconnected-(U1-PD5-Pad119)") (class "Default")
      (node (ref "U1") (pin "119") (pinfunction "PD5_119") (pintype "unspecified"))
    )
    (net (code "107") (name "unconnected-(U1-PD6-Pad122)") (class "Default")
      (node (ref "U1") (pin "122") (pinfunction "PD6_122") (pintype "unspecified"))
    )
    (net (code "108") (name "unconnected-(U1-PD7-Pad123)") (class "Default")
      (node (ref "U1") (pin "123") (pinfunction "PD7_123") (pintype "unspecified"))
    )
    (net (code "109") (name "unconnected-(U1-PD8-Pad77)") (class "Default")
      (node (ref "U1") (pin "77") (pinfunction "PD8_77") (pintype "unspecified"))
    )
    (net (code "110") (name "unconnected-(U1-PD9-Pad78)") (class "Default")
      (node (ref "U1") (pin "78") (pinfunction "PD9_78") (pintype "unspecified"))
    )
    (net (code "111") (name "unconnected-(U1-PD10-Pad79)") (class "Default")
      (node (ref "U1") (pin "79") (pinfunction "PD10_79") (pintype "unspecified"))
    )
    (net (code "112") (name "unconnected-(U1-PD11-Pad80)") (class "Default")
      (node (ref "U1") (pin "80") (pinfunction "PD11_80") (pintype "unspecified"))
    )
    (net (code "113") (name "unconnected-(U1-PD12-Pad81)") (class "Default")
      (node (ref "U1") (pin "81") (pinfunction "PD12_81") (pintype "unspecified"))
    )
    (net (code "114") (name "unconnected-(U1-PD13-Pad82)") (class "Default")
      (node (ref "U1") (pin "82") (pinfunction "PD13_82") (pintype "unspecified"))
    )
    (net (code "115") (name "unconnected-(U1-PD14-Pad85)") (class "Default")
      (node (ref "U1") (pin "85") (pinfunction "PD14_85") (pintype "unspecified"))
    )
    (net (code "116") (name "unconnected-(U1-PD15-Pad86)") (class "Default")
      (node (ref "U1") (pin "86") (pinfunction "PD15_86") (pintype "unspecified"))
    )
    (net (code "117") (name "unconnected-(U1-PE0-Pad141)") (class "Default")
      (node (ref "U1") (pin "141") (pinfunction "PE0_141") (pintype "unspecified"))
    )
    (net (code "118") (name "unconnected-(U1-PE1-Pad142)") (class "Default")
      (node (ref "U1") (pin "142") (pinfunction "PE1_142") (pintype "unspecified"))
    )
    (net (code "119") (name "unconnected-(U1-PE2-Pad1)") (class "Default")
      (node (ref "U1") (pin "1") (pinfunction "PE2_1") (pintype "unspecified"))
    )
    (net (code "120") (name "unconnected-(U1-PE3-Pad2)") (class "Default")
      (node (ref "U1") (pin "2") (pinfunction "PE3_2") (pintype "unspecified"))
    )
    (net (code "121") (name "unconnected-(U1-PE4-Pad3)") (class "Default")
      (node (ref "U1") (pin "3") (pinfunction "PE4_3") (pintype "unspecified"))
    )
    (net (code "122") (name "unconnected-(U1-PE5-Pad4)") (class "Default")
      (node (ref "U1") (pin "4") (pinfunction "PE5_4") (pintype "unspecified"))
    )
    (net (code "123") (name "unconnected-(U1-PE6-Pad5)") (class "Default")
      (node (ref "U1") (pin "5") (pinfunction "PE6_5") (pintype "unspecified"))
    )
    (net (code "124") (name "unconnected-(U1-PE7-Pad58)") (class "Default")
      (node (ref "U1") (pin "58") (pinfunction "PE7_58") (pintype "unspecified"))
    )
    (net (code "125") (name "unconnected-(U1-PE8-Pad59)") (class "Default")
      (node (ref "U1") (pin "59") (pinfunction "PE8_59") (pintype "unspecified"))
    )
    (net (code "126") (name "unconnected-(U1-PE9-Pad60)") (class "Default")
      (node (ref "U1") (pin "60") (pinfunction "PE9_60") (pintype "unspecified"))
    )
    (net (code "127") (name "unconnected-(U1-PE10-Pad63)") (class "Default")
      (node (ref "U1") (pin "63") (pinfunction "PE10_63") (pintype "unspecified"))
    )
    (net (code "128") (name "unconnected-(U1-PE11-Pad64)") (class "Default")
      (node (ref "U1") (pin "64") (pinfunction "PE11_64") (pintype "unspecified"))
    )
    (net (code "129") (name "unconnected-(U1-PE12-Pad65)") (class "Default")
      (node (ref "U1") (pin "65") (pinfunction "PE12_65") (pintype "unspecified"))
    )
    (net (code "130") (name "unconnected-(U1-PE13-Pad66)") (class "Default")
      (node (ref "U1") (pin "66") (pinfunction "PE13_66") (pintype "unspecified"))
    )
    (net (code "131") (name "unconnected-(U1-PE14-Pad67)") (class "Default")
      (node (ref "U1") (pin "67") (pinfunction "PE14_67") (pintype "unspecified"))
    )
    (net (code "132") (name "unconnected-(U1-PE15-Pad68)") (class "Default")
      (node (ref "U1") (pin "68") (pinfunction "PE15_68") (pintype "unspecified"))
    )
    (net (code "133") (name "unconnected-(U1-PF2-Pad12)") (class "Default")
      (node (ref "U1") (pin "12") (pinfunction "PF2_12") (pintype "unspecified"))
    )
    (net (code "134") (name "unconnected-(U1-PF3-Pad13)") (class "Default")
      (node (ref "U1") (pin "13") (pinfunction "PF3_13") (pintype "unspecified"))
    )
    (net (code "135") (name "unconnected-(U1-PF4-Pad14)") (class "Default")
      (node (ref "U1") (pin "14") (pinfunction "PF4_14") (pintype "unspecified"))
    )
    (net (code "136") (name "unconnected-(U1-PF5-Pad15)") (class "Default")
      (node (ref "U1") (pin "15") (pinfunction "PF5_15") (pintype "unspecified"))
    )
    (net (code "137") (name "unconnected-(U1-PF6-Pad18)") (class "Default")
      (node (ref "U1") (pin "18") (pinfunction "PF6_18") (pintype "unspecified"))
    )
    (net (code "138") (name "unconnected-(U1-PF7-Pad19)") (class "Default")
      (node (ref "U1") (pin "19") (pinfunction "PF7_19") (pintype "unspecified"))
    )
    (net (code "139") (name "unconnected-(U1-PF8-Pad20)") (class "Default")
      (node (ref "U1") (pin "20") (pinfunction "PF8_20") (pintype "unspecified"))
    )
    (net (code "140") (name "unconnected-(U1-PF9-Pad21)") (class "Default")
      (node (ref "U1") (pin "21") (pinfunction "PF9_21") (pintype "unspecified"))
    )
    (net (code "141") (name "unconnected-(U1-PF10-Pad22)") (class "Default")
      (node (ref "U1") (pin "22") (pinfunction "PF10_22") (pintype "unspecified"))
    )
    (net (code "142") (name "unconnected-(U1-PF11-Pad49)") (class "Default")
      (node (ref "U1") (pin "49") (pinfunction "PF11_49") (pintype "unspecified"))
    )
    (net (code "143") (name "unconnected-(U1-PF12-Pad50)") (class "Default")
      (node (ref "U1") (pin "50") (pinfunction "PF12_50") (pintype "unspecified"))
    )
    (net (code "144") (name "unconnected-(U1-PF13-Pad53)") (class "Default")
      (node (ref "U1") (pin "53") (pinfunction "PF13_53") (pintype "unspecified"))
    )
    (net (code "145") (name "unconnected-(U1-PF14-Pad54)") (class "Default")
      (node (ref "U1") (pin "54") (pinfunction "PF14_54") (pintype "unspecified"))
    )
    (net (code "146") (name "unconnected-(U1-PF15-Pad55)") (class "Default")
      (node (ref "U1") (pin "55") (pinfunction "PF15_55") (pintype "unspecified"))
    )
    (net (code "147") (name "unconnected-(U1-PG0-Pad56)") (class "Default")
      (node (ref "U1") (pin "56") (pinfunction "PG0_56") (pintype "unspecified"))
    )
    (net (code "148") (name "unconnected-(U1-PG1-Pad57)") (class "Default")
      (node (ref "U1") (pin "57") (pinfunction "PG1_57") (pintype "unspecified"))
    )
    (net (code "149") (name "unconnected-(U1-PG2-Pad87)") (class "Default")
      (node (ref "U1") (pin "87") (pinfunction "PG2_87") (pintype "unspecified"))
    )
    (net (code "150") (name "unconnected-(U1-PG3-Pad88)") (class "Default")
      (node (ref "U1") (pin "88") (pinfunction "PG3_88") (pintype "unspecified"))
    )
    (net (code "151") (name "unconnected-(U1-PG4-Pad89)") (class "Default")
      (node (ref "U1") (pin "89") (pinfunction "PG4_89") (pintype "unspecified"))
    )
    (net (code "152") (name "unconnected-(U1-PG5-Pad90)") (class "Default")
      (node (ref "U1") (pin "90") (pinfunction "PG5_90") (pintype "unspecified"))
    )
    (net (code "153") (name "unconnected-(U1-PG6-Pad91)") (class "Default")
      (node (ref "U1") (pin "91") (pinfunction "PG6_91") (pintype "unspecified"))
    )
    (net (code "154") (name "unconnected-(U1-PG7-Pad92)") (class "Default")
      (node (ref "U1") (pin "92") (pinfunction "PG7_92") (pintype "unspecified"))
    )
    (net (code "155") (name "unconnected-(U1-PG8-Pad93)") (class "Default")
      (node (ref "U1") (pin "93") (pinfunction "PG8_93") (pintype "unspecified"))
    )
    (net (code "156") (name "unconnected-(U1-PG9-Pad124)") (class "Default")
      (node (ref "U1") (pin "124") (pinfunction "PG9_124") (pintype "unspecified"))
    )
    (net (code "157") (name "unconnected-(U1-PG10-Pad125)") (class "Default")
      (node (ref "U1") (pin "125") (pinfunction "PG10_125") (pintype "unspecified"))
    )
    (net (code "158") (name "unconnected-(U1-PG11-Pad126)") (class "Default")
      (node (ref "U1") (pin "126") (pinfunction "PG11_126") (pintype "unspecified"))
    )
    (net (code "159") (name "unconnected-(U1-PG12-Pad127)") (class "Default")
      (node (ref "U1") (pin "127") (pinfunction "PG12_127") (pintype "unspecified"))
    )
    (net (code "160") (name "unconnected-(U1-PG13-Pad128)") (class "Default")
      (node (ref "U1") (pin "128") (pinfunction "PG13_128") (pintype "unspecified"))
    )
    (net (code "161") (name "unconnected-(U1-PG14-Pad129)") (class "Default")
      (node (ref "U1") (pin "129") (pinfunction "PG14_129") (pintype "unspecified"))
    )
    (net (code "162") (name "unconnected-(U1-PG15-Pad132)") (class "Default")
      (node (ref "U1") (pin "132") (pinfunction "PG15_132") (pintype "unspecified"))
    )
    (net (code "163") (name "unconnected-(U1-PH0-Pad23)") (class "Default")
      (node (ref "U1") (pin "23") (pinfunction "PH0_23") (pintype "unspecified"))
    )
    (net (code "164") (name "unconnected-(U1-PH1-Pad24)") (class "Default")
      (node (ref "U1") (pin "24") (pinfunction "PH1_24") (pintype "unspecified"))
    )
    (net (code "165") (name "unconnected-(U3-DJ9-Pad26)") (class "Default")
      (node (ref "U3") (pin "26") (pinfunction "DJ9_26") (pintype "input"))
    )
    (net (code "166") (name "unconnected-(U3-DJ10-Pad27)") (class "Default")
      (node (ref "U3") (pin "27") (pinfunction "DJ10_27") (pintype "input"))
    )
    (net (code "167") (name "unconnected-(U3-DJ11-Pad28)") (class "Default")
      (node (ref "U3") (pin "28") (pinfunction "DJ11_28") (pintype "input"))
    )
    (net (code "168") (name "unconnected-(U3-DJ12-Pad29)") (class "Default")
      (node (ref "U3") (pin "29") (pinfunction "DJ12_29") (pintype "input"))
    )
    (net (code "169") (name "unconnected-(U3-DJ13-Pad30)") (class "Default")
      (node (ref "U3") (pin "30") (pinfunction "DJ13_30") (pintype "input"))
    )
    (net (code "170") (name "unconnected-(U3-DJ14-Pad31)") (class "Default")
      (node (ref "U3") (pin "31") (pinfunction "DJ14_31") (pintype "input"))
    )
    (net (code "171") (name "unconnected-(U3-DJ15-Pad32)") (class "Default")
      (node (ref "U3") (pin "32") (pinfunction "DJ15_32") (pintype "input"))
    )
    (net (code "172") (name "unconnected-(U3-DJ16-Pad1)") (class "Default")
      (node (ref "U3") (pin "1") (pinfunction "DJ16_1") (pintype "input+no_connect"))
    )
    (net (code "173") (name "unconnected-(U3-DJ17-Pad2)") (class "Default")
      (node (ref "U3") (pin "2") (pinfunction "DJ17_2") (pintype "input+no_connect"))
    )
    (net (code "174") (name "unconnected-(U3-DJ18-Pad3)") (class "Default")
      (node (ref "U3") (pin "3") (pinfunction "DJ18_3") (pintype "input+no_connect"))
    )
    (net (code "175") (name "unconnected-(U3-DJ19-Pad4)") (class "Default")
      (node (ref "U3") (pin "4") (pinfunction "DJ19_4") (pintype "input+no_connect"))
    )
    (net (code "176") (name "unconnected-(U3-RXD-Pad13)") (class "Default")
      (node (ref "U3") (pin "13") (pinfunction "RXD_13") (pintype "input+no_connect"))
    )
    (net (code "177") (name "unconnected-(U3-TXD-Pad14)") (class "Default")
      (node (ref "U3") (pin "14") (pinfunction "TXD_14") (pintype "input+no_connect"))
    )
    (net (code "178") (name "unconnected-(U14-DJ9-Pad26)") (class "Default")
      (node (ref "U14") (pin "26") (pinfunction "DJ9_26") (pintype "input"))
    )
    (net (code "179") (name "unconnected-(U14-DJ10-Pad27)") (class "Default")
      (node (ref "U14") (pin "27") (pinfunction "DJ10_27") (pintype "input"))
    )
    (net (code "180") (name "unconnected-(U14-DJ11-Pad28)") (class "Default")
      (node (ref "U14") (pin "28") (pinfunction "DJ11_28") (pintype "input"))
    )
    (net (code "181") (name "unconnected-(U14-DJ12-Pad29)") (class "Default")
      (node (ref "U14") (pin "29") (pinfunction "DJ12_29") (pintype "input"))
    )
    (net (code "182") (name "unconnected-(U14-DJ13-Pad30)") (class "Default")
      (node (ref "U14") (pin "30") (pinfunction "DJ13_30") (pintype "input"))
    )
    (net (code "183") (name "unconnected-(U14-DJ14-Pad31)") (class "Default")
      (node (ref "U14") (pin "31") (pinfunction "DJ14_31") (pintype "input"))
    )
    (net (code "184") (name "unconnected-(U14-DJ15-Pad32)") (class "Default")
      (node (ref "U14") (pin "32") (pinfunction "DJ15_32") (pintype "input"))
    )
    (net (code "185") (name "unconnected-(U14-DJ16-Pad1)") (class "Default")
      (node (ref "U14") (pin "1") (pinfunction "DJ16_1") (pintype "input+no_connect"))
    )
    (net (code "186") (name "unconnected-(U14-DJ17-Pad2)") (class "Default")
      (node (ref "U14") (pin "2") (pinfunction "DJ17_2") (pintype "input+no_connect"))
    )
    (net (code "187") (name "unconnected-(U14-DJ18-Pad3)") (class "Default")
      (node (ref "U14") (pin "3") (pinfunction "DJ18_3") (pintype "input+no_connect"))
    )
    (net (code "188") (name "unconnected-(U14-DJ19-Pad4)") (class "Default")
      (node (ref "U14") (pin "4") (pinfunction "DJ19_4") (pintype "input+no_connect"))
    )
    (net (code "189") (name "unconnected-(U14-RXD-Pad13)") (class "Default")
      (node (ref "U14") (pin "13") (pinfunction "RXD_13") (pintype "input+no_connect"))
    )
    (net (code "190") (name "unconnected-(U14-TXD-Pad14)") (class "Default")
      (node (ref "U14") (pin "14") (pinfunction "TXD_14") (pintype "input+no_connect"))
    )
    (net (code "191") (name "unconnected-(U19-ENA-Pad5)") (class "Default")
      (node (ref "U19") (pin "5") (pinfunction "ENA_5") (pintype "unspecified+no_connect"))
    )
    (net (code "192") (name "unconnected-(U19-NC-Pad2)") (class "Default")
      (node (ref "U19") (pin "2") (pinfunction "NC_2") (pintype "unspecified+no_connect"))
    )
    (net (code "193") (name "unconnected-(U19-NC-Pad3)") (class "Default")
      (node (ref "U19") (pin "3") (pinfunction "NC_3") (pintype "unspecified+no_connect"))
    )
    (net (code "194") (name "unconnected-(U28-AUX_CL-Pad7)") (class "Default")
      (node (ref "U28") (pin "7") (pinfunction "AUX_CL_7") (pintype "input"))
    )
    (net (code "195") (name "unconnected-(U28-AUX_DA-Pad6)") (class "Default")
      (node (ref "U28") (pin "6") (pinfunction "AUX_DA_6") (pintype "input"))
    )
    (net (code "196") (name "unconnected-(U28-INT-Pad12)") (class "Default")
      (node (ref "U28") (pin "12") (pinfunction "INT_12") (pintype "input"))
    )
    (net (code "197") (name "unconnected-(U28-NC-Pad2)") (class "Default")
      (node (ref "U28") (pin "2") (pinfunction "NC_2") (pintype "input"))
    )
    (net (code "198") (name "unconnected-(U28-NC-Pad3)") (class "Default")
      (node (ref "U28") (pin "3") (pinfunction "NC_3") (pintype "input"))
    )
    (net (code "199") (name "unconnected-(U28-NC-Pad4)") (class "Default")
      (node (ref "U28") (pin "4") (pinfunction "NC_4") (pintype "input"))
    )
    (net (code "200") (name "unconnected-(U28-NC-Pad5)") (class "Default")
      (node (ref "U28") (pin "5") (pinfunction "NC_5") (pintype "input"))
    )
    (net (code "201") (name "unconnected-(U28-NC-Pad14)") (class "Default")
      (node (ref "U28") (pin "14") (pinfunction "NC_14") (pintype "input"))
    )
    (net (code "202") (name "unconnected-(U28-NC-Pad15)") (class "Default")
      (node (ref "U28") (pin "15") (pinfunction "NC_15") (pintype "input"))
    )
    (net (code "203") (name "unconnected-(U28-NC-Pad16)") (class "Default")
      (node (ref "U28") (pin "16") (pinfunction "NC_16") (pintype "input"))
    )
    (net (code "204") (name "unconnected-(U28-NC-Pad17)") (class "Default")
      (node (ref "U28") (pin "17") (pinfunction "NC_17") (pintype "input"))
    )
    (net (code "205") (name "unconnected-(U28-RESV-Pad19)") (class "Default")
      (node (ref "U28") (pin "19") (pinfunction "RESV_19") (pintype "input"))
    )
    (net (code "206") (name "unconnected-(U28-RESV-Pad21)") (class "Default")
      (node (ref "U28") (pin "21") (pinfunction "RESV_21") (pintype "input"))
    )
    (net (code "207") (name "unconnected-(U28-RESV-Pad22)") (class "Default")
      (node (ref "U28") (pin "22") (pinfunction "RESV_22") (pintype "input"))
    )
  )
)
